# SCH_ONO_R1.net
KiCad netlist of a schematic drawn in EasyEDA
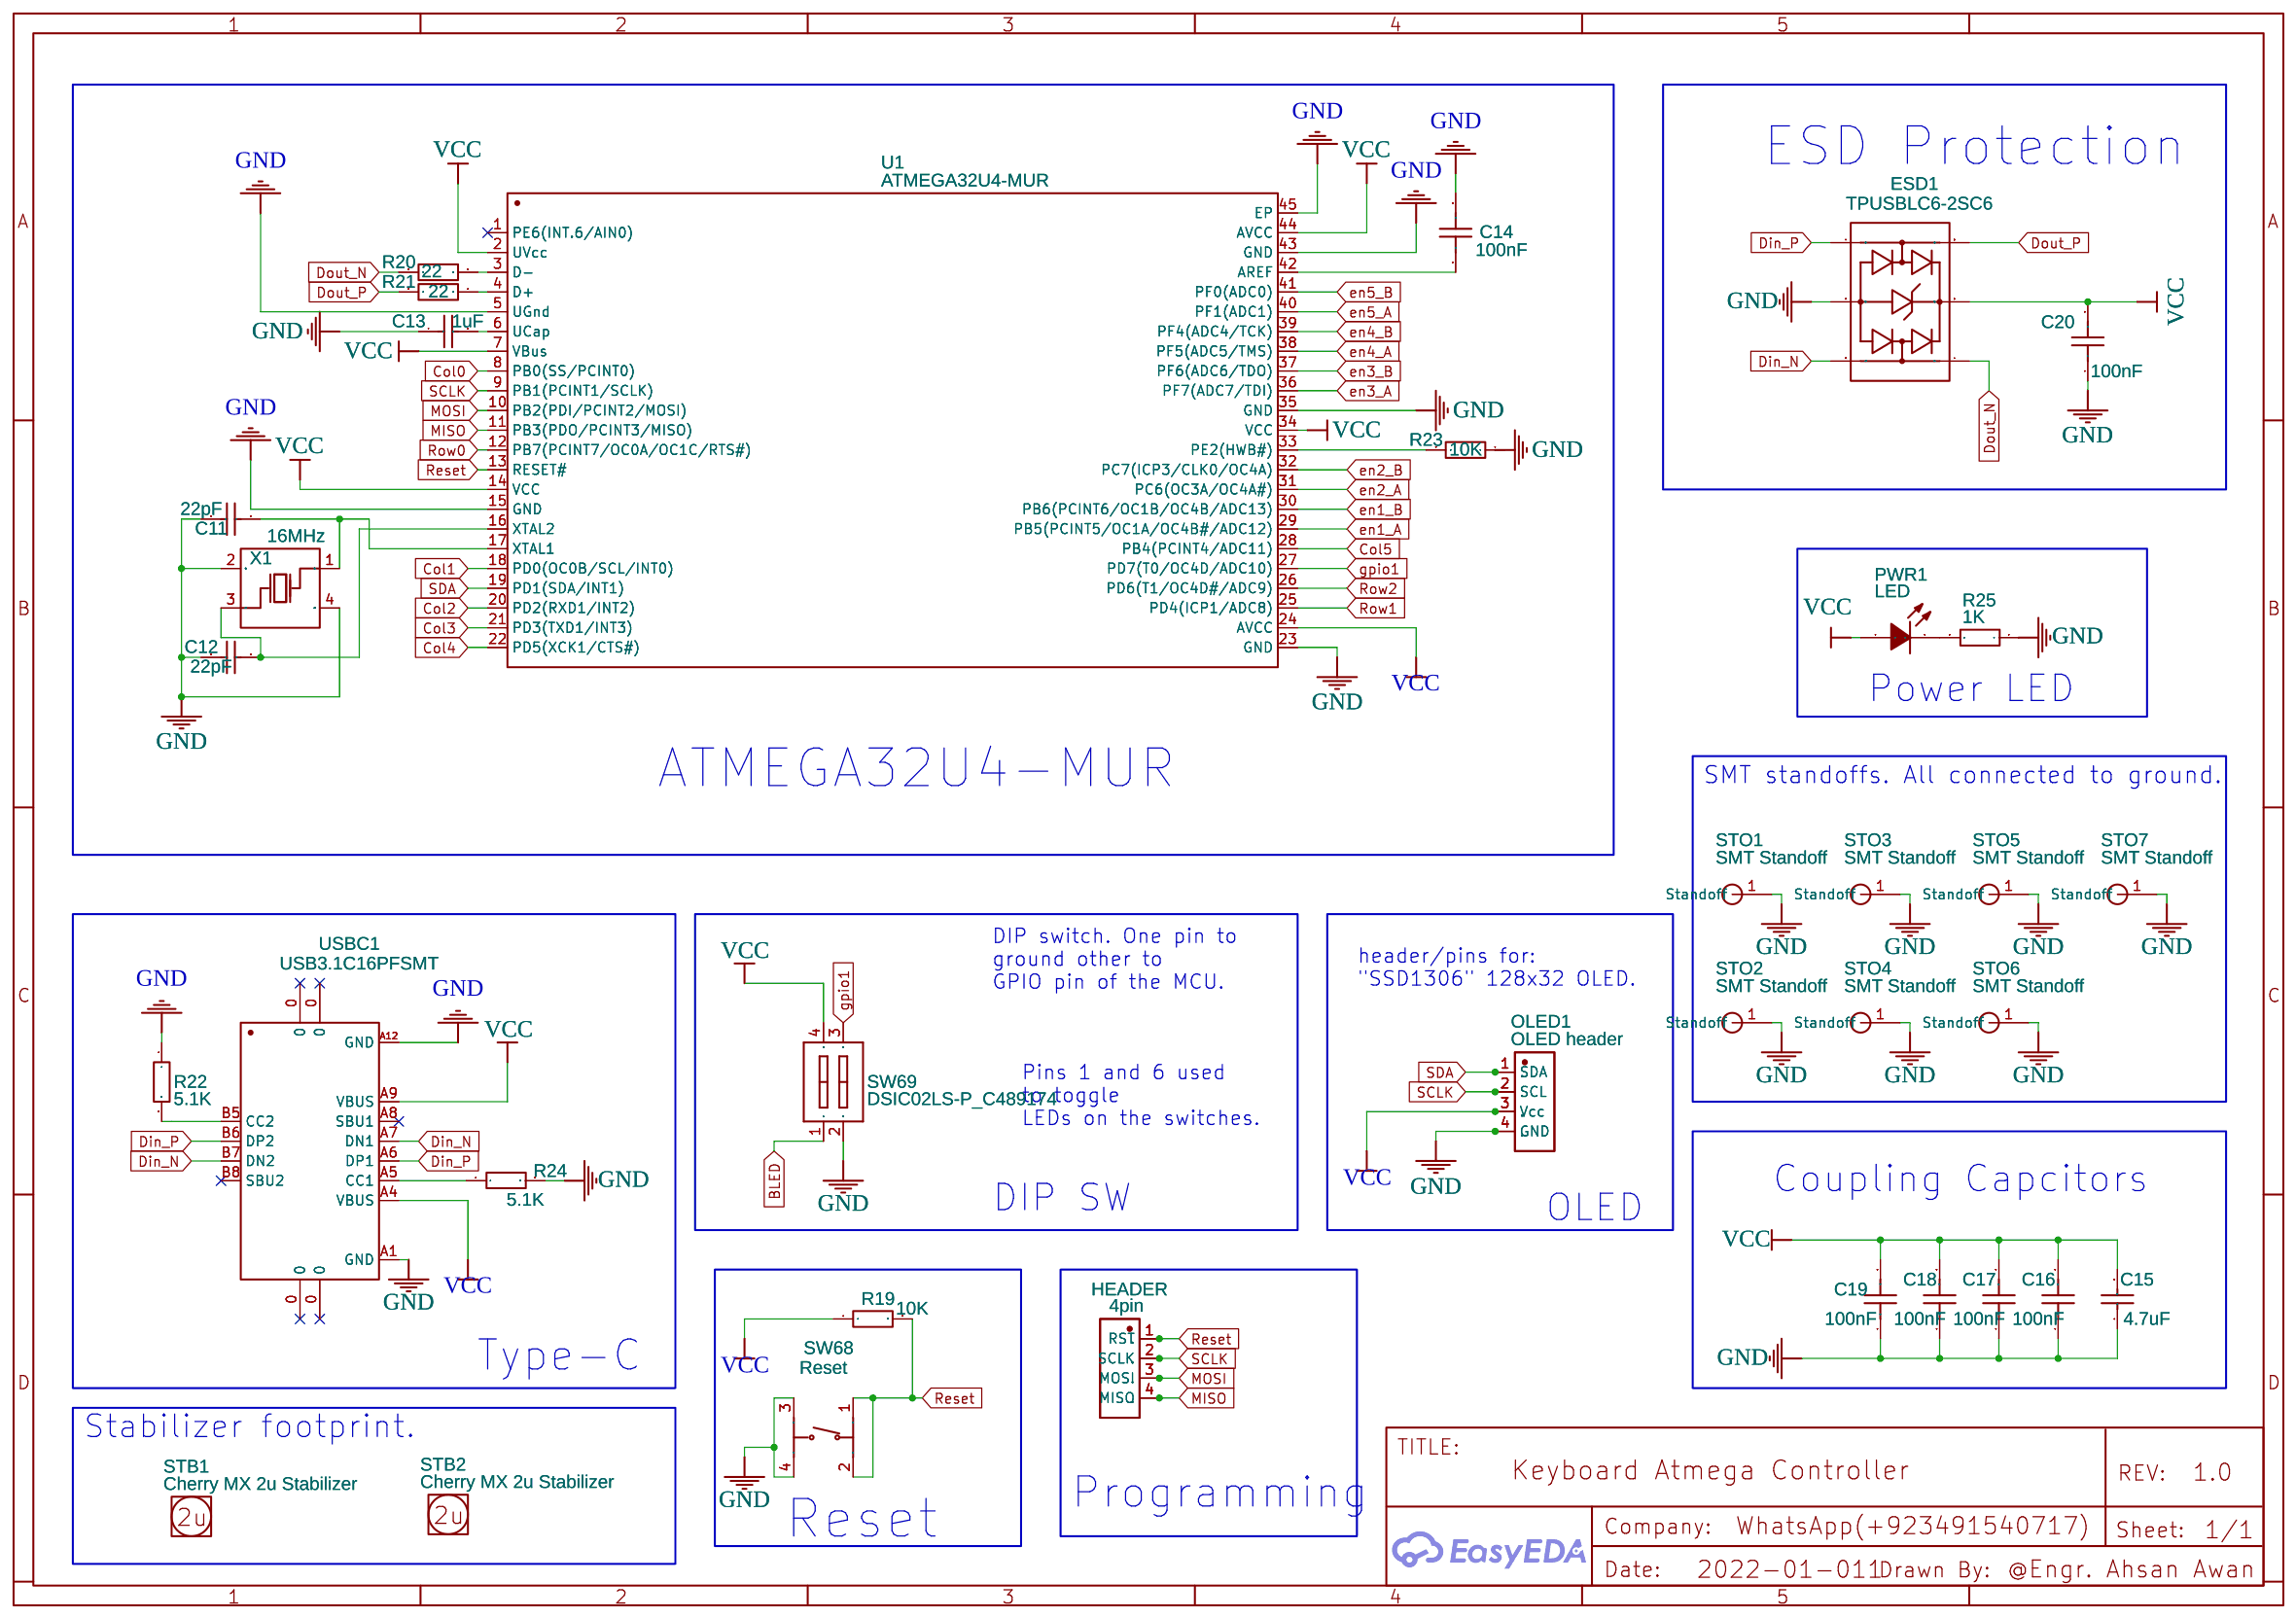
[diagram p0: Atmega MCU]
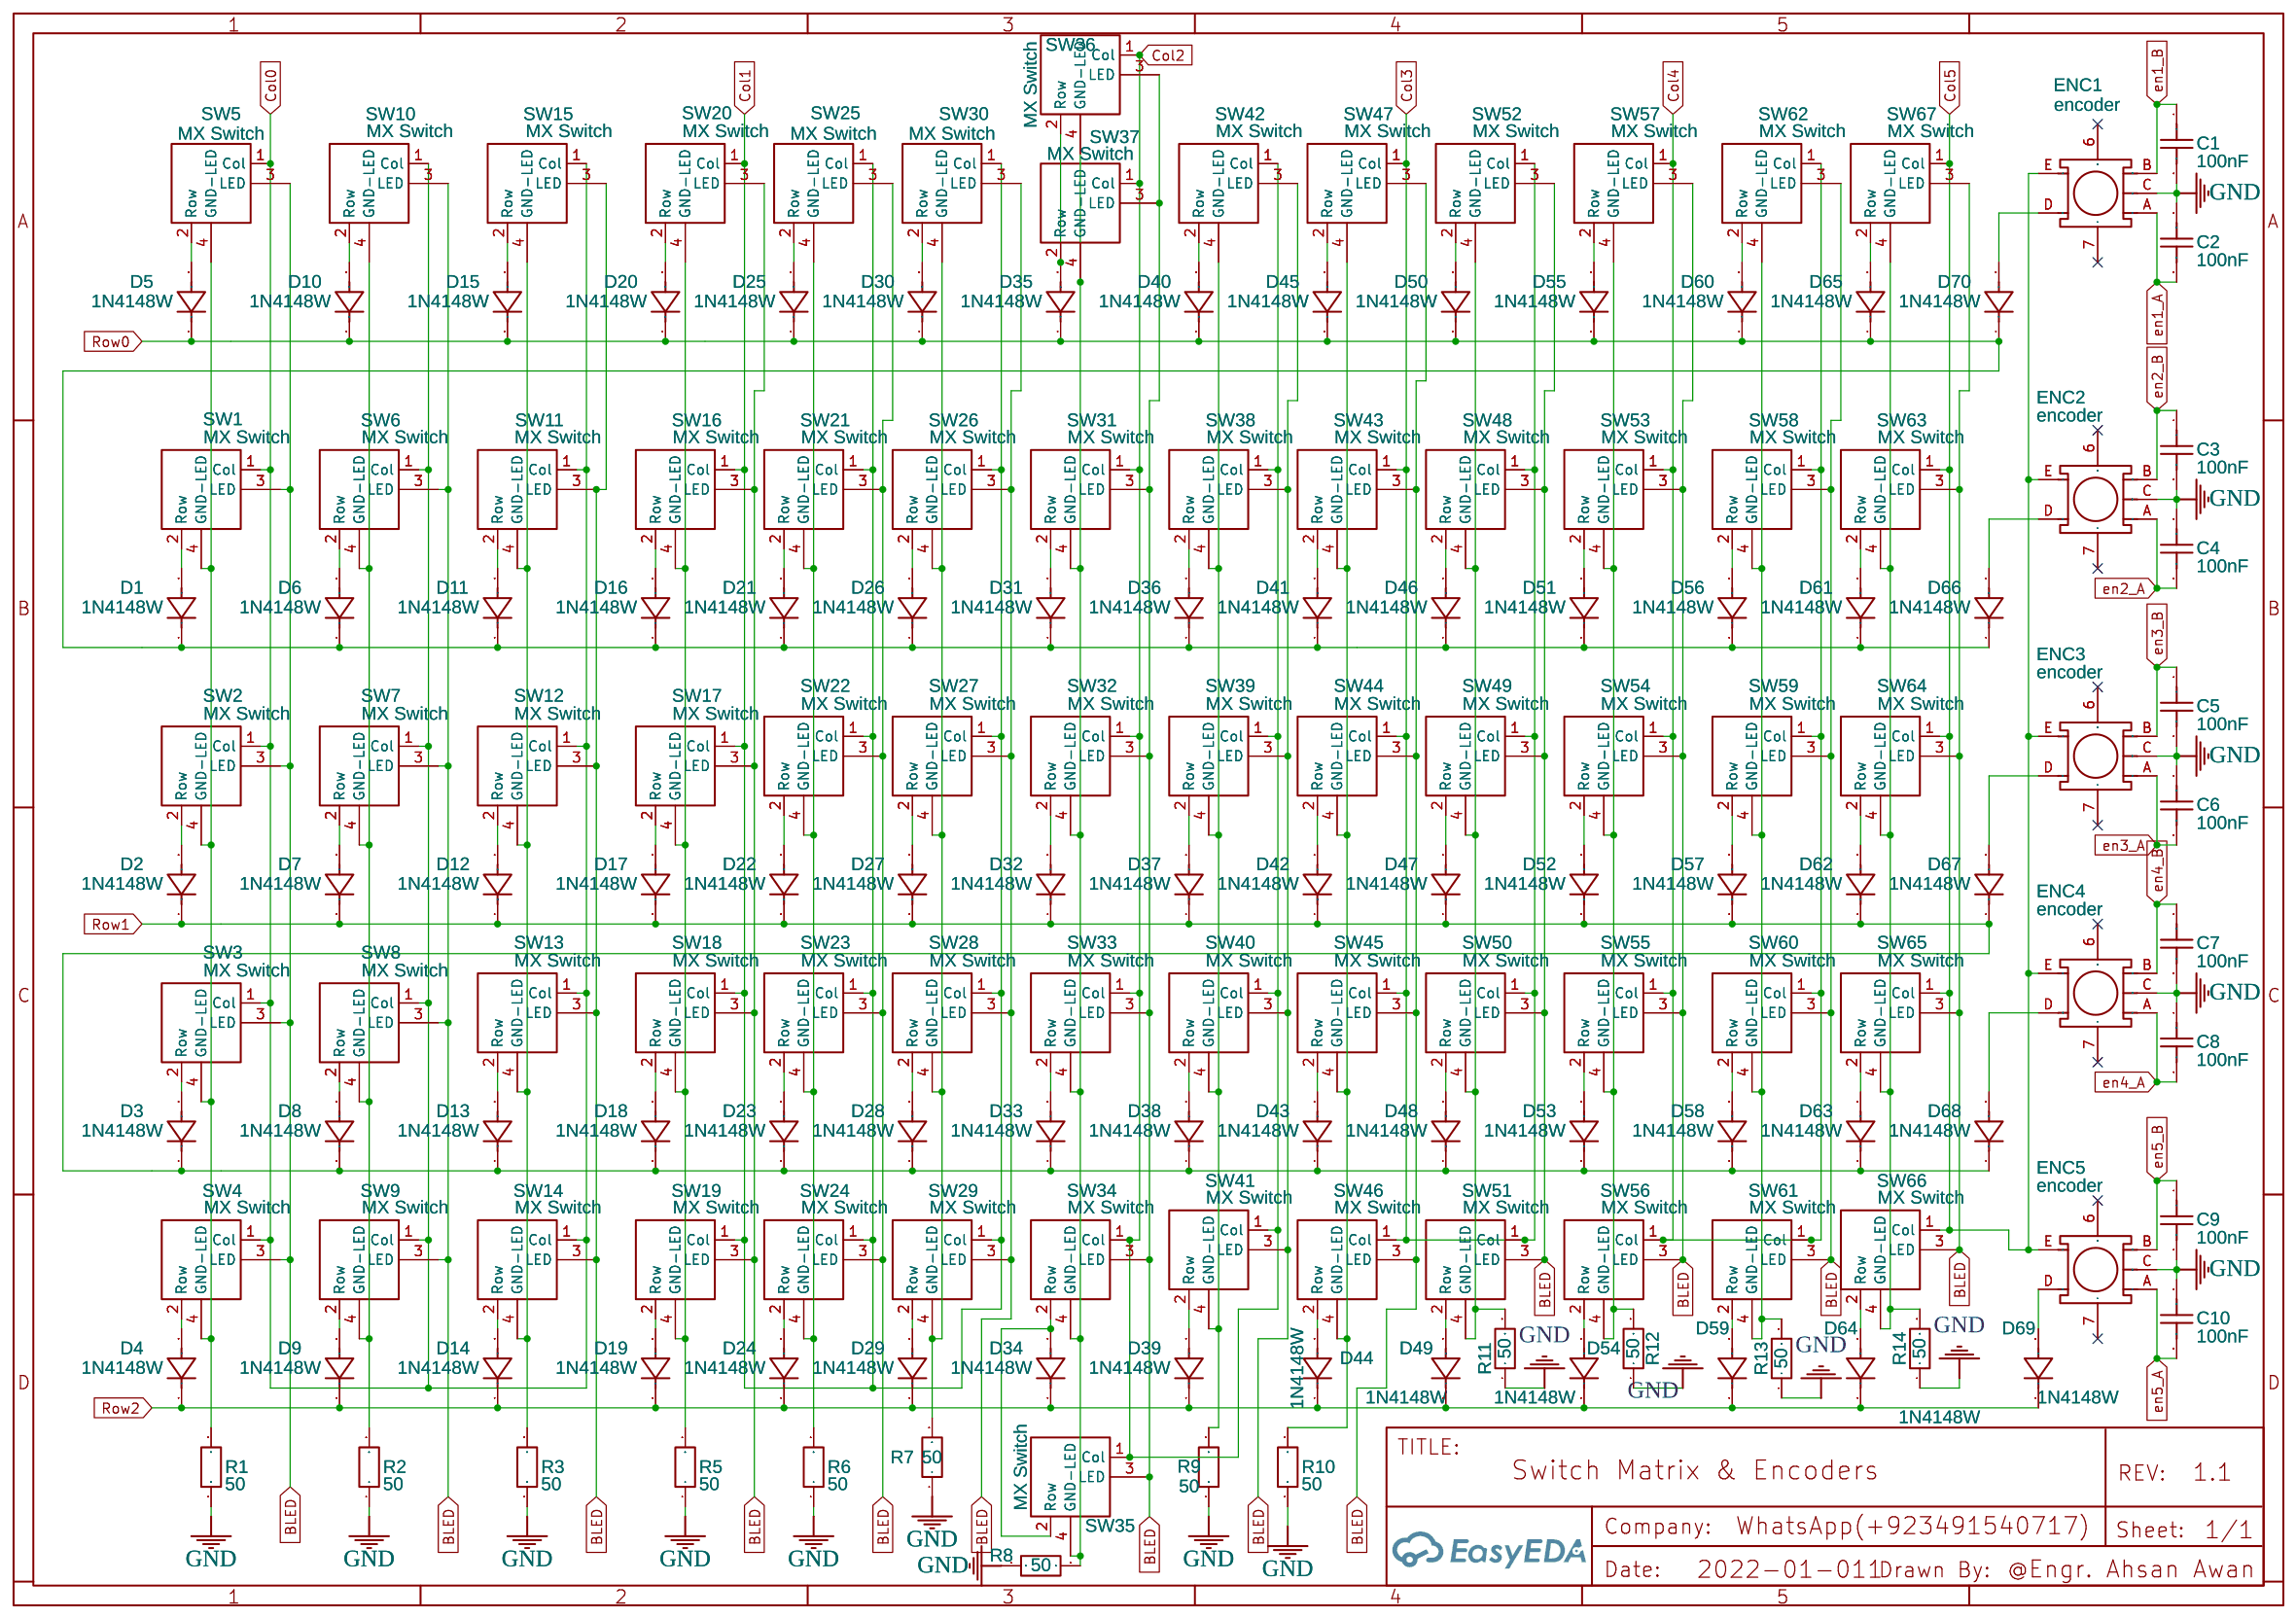
[diagram p1: Switch Matrix]

(export (version "E")
  (design (tool "Eeschema 10.0.6"))
  (components
    (comp (ref "C11")
      (value "22pF")
      (fields
        (field (name "BOM_Manufacturer Part") "CL10C220JB8NNNC")
        (field (name "BOM_Supplier Part") "C1653")
      )
      (libsource (lib "") (part "CL10C220JB8NNNC"))
    )
    (comp (ref "C12")
      (value "22pF")
      (fields
        (field (name "BOM_Manufacturer Part") "CL10C220JB8NNNC")
        (field (name "BOM_Supplier Part") "C1653")
      )
      (libsource (lib "") (part "CL10C220JB8NNNC"))
    )
    (comp (ref "C13")
      (value "1uF")
      (fields
        (field (name "BOM_Manufacturer Part") "CL10A105KB8NNNC")
        (field (name "BOM_Supplier Part") "C15849")
      )
      (libsource (lib "") (part "CL10A105KB8NNNC"))
    )
    (comp (ref "C14")
      (value "100nF")
      (fields
        (field (name "BOM_Manufacturer Part") "CC0603KRX7R9BB104")
        (field (name "BOM_Supplier Part") "C14663")
      )
      (libsource (lib "") (part "CC0603KRX7R9BB104"))
    )
    (comp (ref "C15")
      (value "4.7uF")
      (fields
        (field (name "BOM_Manufacturer Part") "CL10A475KO8NNNC")
        (field (name "BOM_Supplier Part") "C19666")
      )
      (libsource (lib "") (part "CL10A475KO8NNNC"))
    )
    (comp (ref "C16")
      (value "100nF")
      (fields
        (field (name "BOM_Manufacturer Part") "CC0603KRX7R9BB104")
        (field (name "BOM_Supplier Part") "C14663")
      )
      (libsource (lib "") (part "CC0603KRX7R9BB104"))
    )
    (comp (ref "C17")
      (value "100nF")
      (fields
        (field (name "BOM_Manufacturer Part") "CC0603KRX7R9BB104")
        (field (name "BOM_Supplier Part") "C14663")
      )
      (libsource (lib "") (part "CC0603KRX7R9BB104"))
    )
    (comp (ref "C18")
      (value "100nF")
      (fields
        (field (name "BOM_Manufacturer Part") "CC0603KRX7R9BB104")
        (field (name "BOM_Supplier Part") "C14663")
      )
      (libsource (lib "") (part "CC0603KRX7R9BB104"))
    )
    (comp (ref "C19")
      (value "100nF")
      (fields
        (field (name "BOM_Manufacturer Part") "CC0603KRX7R9BB104")
        (field (name "BOM_Supplier Part") "C14663")
      )
      (libsource (lib "") (part "CC0603KRX7R9BB104"))
    )
    (comp (ref "C20")
      (value "100nF")
      (fields
        (field (name "BOM_Manufacturer Part") "CC0603KRX7R9BB104")
        (field (name "BOM_Supplier Part") "C14663")
      )
      (libsource (lib "") (part "CC0603KRX7R9BB104"))
    )
    (comp (ref "ESD1")
      (value "TPUSBLC6-2SC6")
      (fields (field (name "BOM_Supplier Part") "C558442"))
      (libsource (lib "") (part "TPUSBLC6-2SC6"))
    )
    (comp (ref "HEADER")
      (value "4pin")
      (fields
        (field (name "BOM_Manufacturer Part") "X4611WRS-04I-C40D28")
        (field (name "BOM_Supplier Part") "C917591")
      )
      (libsource (lib "") (part "X4611WRS-04I-C40D28_1"))
    )
    (comp (ref "OLED1")
      (value "OLED header")
      (fields
        (field (name "BOM_Manufacturer Part") "X4611WRS-04I-C40D28")
        (field (name "BOM_Supplier Part") "C917591")
      )
      (libsource (lib "") (part "X4611WRS-04I-C40D28"))
    )
    (comp (ref "PWR1")
      (value "LED")
      (fields
        (field (name "BOM_Manufacturer Part") "TJ-S2012SW8TGLC6B-A5")
        (field (name "BOM_Supplier Part") "C192320")
      )
      (libsource (lib "") (part "TJ-S2012SW8TGLC6B-A5"))
    )
    (comp (ref "R19")
      (value "10K")
      (fields
        (field (name "BOM_Manufacturer Part") "0603WAF1002T5E")
        (field (name "BOM_Supplier Part") "C25804")
      )
      (libsource (lib "") (part "0603WAF1002T5E_1"))
    )
    (comp (ref "R20")
      (value "22")
      (fields
        (field (name "BOM_Manufacturer Part") "0603WAF220JT5E")
        (field (name "BOM_Supplier Part") "C23345")
      )
      (libsource (lib "") (part "0603WAF220JT5E"))
    )
    (comp (ref "R21")
      (value "22")
      (fields
        (field (name "BOM_Manufacturer Part") "0603WAF220JT5E")
        (field (name "BOM_Supplier Part") "C23345")
      )
      (libsource (lib "") (part "0603WAF220JT5E"))
    )
    (comp (ref "R22")
      (value "5.1K")
      (fields
        (field (name "BOM_Manufacturer Part") "RMC06035.1K1%N")
        (field (name "BOM_Supplier Part") "C269716")
      )
      (libsource (lib "") (part "RMC06035.1K1%N_1"))
    )
    (comp (ref "R23")
      (value "10K")
      (fields
        (field (name "BOM_Manufacturer Part") "0603WAF1002T5E")
        (field (name "BOM_Supplier Part") "C25804")
      )
      (libsource (lib "") (part "0603WAF1002T5E"))
    )
    (comp (ref "R24")
      (value "5.1K")
      (fields
        (field (name "BOM_Manufacturer Part") "RMC06035.1K1%N")
        (field (name "BOM_Supplier Part") "C269716")
      )
      (libsource (lib "") (part "RMC06035.1K1%N"))
    )
    (comp (ref "R25")
      (value "1K")
      (fields
        (field (name "BOM_Manufacturer Part") "TR0603B1KP0525")
        (field (name "BOM_Supplier Part") "C188364")
      )
      (libsource (lib "") (part "TR0603B1KP0525"))
    )
    (comp (ref "STB1")
      (value "Cherry MX 2u Stabilizer")
      (fields
        (field (name "BOM_Manufacturer Part") "G99-0742")
        (field (name "BOM_Supplier Part") "540-G99-0742")
      )
      (libsource (lib "") (part "Cherry MX 2u Stabilizer"))
    )
    (comp (ref "STB2")
      (value "Cherry MX 2u Stabilizer")
      (fields
        (field (name "BOM_Manufacturer Part") "G99-0742")
        (field (name "BOM_Supplier Part") "540-G99-0742")
      )
      (libsource (lib "") (part "Cherry MX 2u Stabilizer"))
    )
    (comp (ref "STO1")
      (value "SMT Standoff")
      (fields (field (name "BOM_Manufacturer Part") "9774040151R"))
      (libsource (lib "") (part "SMT Standoff"))
    )
    (comp (ref "STO2")
      (value "SMT Standoff")
      (fields (field (name "BOM_Manufacturer Part") "9774040151R"))
      (libsource (lib "") (part "SMT Standoff"))
    )
    (comp (ref "STO3")
      (value "SMT Standoff")
      (fields (field (name "BOM_Manufacturer Part") "9774040151R"))
      (libsource (lib "") (part "SMT Standoff"))
    )
    (comp (ref "STO4")
      (value "SMT Standoff")
      (fields (field (name "BOM_Manufacturer Part") "9774040151R"))
      (libsource (lib "") (part "SMT Standoff"))
    )
    (comp (ref "STO5")
      (value "SMT Standoff")
      (fields (field (name "BOM_Manufacturer Part") "9774040151R"))
      (libsource (lib "") (part "SMT Standoff"))
    )
    (comp (ref "STO6")
      (value "SMT Standoff")
      (fields (field (name "BOM_Manufacturer Part") "9774040151R"))
      (libsource (lib "") (part "SMT Standoff"))
    )
    (comp (ref "STO7")
      (value "SMT Standoff")
      (fields (field (name "BOM_Manufacturer Part") "9774040151R"))
      (libsource (lib "") (part "SMT Standoff"))
    )
    (comp (ref "SW68")
      (value "Reset")
      (fields
        (field (name "BOM_Manufacturer Part") "TS-1187A-B-A-B")
        (field (name "BOM_Supplier Part") "C318884")
      )
      (libsource (lib "") (part "TS-1187A-B-A-B"))
    )
    (comp (ref "SW69")
      (value "DSIC02LS-P_C489174")
      (fields
        (field (name "BOM_Manufacturer Part") "DSIC02LS-P")
        (field (name "BOM_Supplier Part") "C489174")
      )
      (libsource (lib "") (part "DSIC02LS-P_C489174"))
    )
    (comp (ref "U1")
      (value "ATMEGA32U4-MUR")
      (fields (field (name "BOM_Supplier Part") "C45874"))
      (libsource (lib "") (part "ATMEGA32U4-MUR"))
    )
    (comp (ref "U2")
      (value "x")
      (fields
        (field (name "BOM_Manufacturer Part") "PZ2.54-1X4P-ZW")
        (field (name "BOM_Supplier Part") "C2837836")
      )
      (libsource (lib "") (part "PZ2.54-1X4P-ZW"))
    )
    (comp (ref "U3")
      (value "x")
      (fields
        (field (name "BOM_Manufacturer Part") "PZ2.54-1X4P-ZW")
        (field (name "BOM_Supplier Part") "C2837836")
      )
      (libsource (lib "") (part "PZ2.54-1X4P-ZW_1"))
    )
    (comp (ref "USBC1")
      (value "USB3.1C16PFSMT")
      (fields (field (name "BOM_Supplier Part") "C167321"))
      (libsource (lib "") (part "USB3.1C16PFSMT"))
    )
    (comp (ref "X1")
      (value "16MHz")
      (fields
        (field (name "BOM_Manufacturer Part") "X322516MLB4SI")
        (field (name "BOM_Supplier Part") "C13738")
      )
      (libsource (lib "") (part "X322516MLB4SI"))
    )
    (comp (ref "C1")
      (value "100nF")
      (fields
        (field (name "BOM_Manufacturer Part") "CC0603KRX7R9BB104")
        (field (name "BOM_Supplier Part") "C14663")
      )
      (libsource (lib "") (part "CC0603KRX7R9BB104"))
    )
    (comp (ref "C2")
      (value "100nF")
      (fields
        (field (name "BOM_Manufacturer Part") "CC0603KRX7R9BB104")
        (field (name "BOM_Supplier Part") "C14663")
      )
      (libsource (lib "") (part "CC0603KRX7R9BB104"))
    )
    (comp (ref "C3")
      (value "100nF")
      (fields
        (field (name "BOM_Manufacturer Part") "CC0603KRX7R9BB104")
        (field (name "BOM_Supplier Part") "C14663")
      )
      (libsource (lib "") (part "CC0603KRX7R9BB104"))
    )
    (comp (ref "C4")
      (value "100nF")
      (fields
        (field (name "BOM_Manufacturer Part") "CC0603KRX7R9BB104")
        (field (name "BOM_Supplier Part") "C14663")
      )
      (libsource (lib "") (part "CC0603KRX7R9BB104"))
    )
    (comp (ref "C5")
      (value "100nF")
      (fields
        (field (name "BOM_Manufacturer Part") "CC0603KRX7R9BB104")
        (field (name "BOM_Supplier Part") "C14663")
      )
      (libsource (lib "") (part "CC0603KRX7R9BB104"))
    )
    (comp (ref "C6")
      (value "100nF")
      (fields
        (field (name "BOM_Manufacturer Part") "CC0603KRX7R9BB104")
        (field (name "BOM_Supplier Part") "C14663")
      )
      (libsource (lib "") (part "CC0603KRX7R9BB104"))
    )
    (comp (ref "C7")
      (value "100nF")
      (fields
        (field (name "BOM_Manufacturer Part") "CC0603KRX7R9BB104")
        (field (name "BOM_Supplier Part") "C14663")
      )
      (libsource (lib "") (part "CC0603KRX7R9BB104"))
    )
    (comp (ref "C8")
      (value "100nF")
      (fields
        (field (name "BOM_Manufacturer Part") "CC0603KRX7R9BB104")
        (field (name "BOM_Supplier Part") "C14663")
      )
      (libsource (lib "") (part "CC0603KRX7R9BB104"))
    )
    (comp (ref "C9")
      (value "100nF")
      (fields
        (field (name "BOM_Manufacturer Part") "CC0603KRX7R9BB104")
        (field (name "BOM_Supplier Part") "C14663")
      )
      (libsource (lib "") (part "CC0603KRX7R9BB104"))
    )
    (comp (ref "C10")
      (value "100nF")
      (fields
        (field (name "BOM_Manufacturer Part") "CC0603KRX7R9BB104")
        (field (name "BOM_Supplier Part") "C14663")
      )
      (libsource (lib "") (part "CC0603KRX7R9BB104"))
    )
    (comp (ref "D1")
      (value "1N4148W")
      (fields (field (name "BOM_Supplier Part") "C2828417"))
      (libsource (lib "") (part "1N4148W_C2828417"))
    )
    (comp (ref "D2")
      (value "1N4148W")
      (fields (field (name "BOM_Supplier Part") "C2828417"))
      (libsource (lib "") (part "1N4148W_C2828417"))
    )
    (comp (ref "D3")
      (value "1N4148W")
      (fields (field (name "BOM_Supplier Part") "C2828417"))
      (libsource (lib "") (part "1N4148W_C2828417"))
    )
    (comp (ref "D4")
      (value "1N4148W")
      (fields (field (name "BOM_Supplier Part") "C2828417"))
      (libsource (lib "") (part "1N4148W_C2828417"))
    )
    (comp (ref "D5")
      (value "1N4148W")
      (fields (field (name "BOM_Supplier Part") "C2828417"))
      (libsource (lib "") (part "1N4148W_C2828417"))
    )
    (comp (ref "D6")
      (value "1N4148W")
      (fields (field (name "BOM_Supplier Part") "C2828417"))
      (libsource (lib "") (part "1N4148W_C2828417"))
    )
    (comp (ref "D7")
      (value "1N4148W")
      (fields (field (name "BOM_Supplier Part") "C2828417"))
      (libsource (lib "") (part "1N4148W_C2828417"))
    )
    (comp (ref "D8")
      (value "1N4148W")
      (fields (field (name "BOM_Supplier Part") "C2828417"))
      (libsource (lib "") (part "1N4148W_C2828417"))
    )
    (comp (ref "D9")
      (value "1N4148W")
      (fields (field (name "BOM_Supplier Part") "C2828417"))
      (libsource (lib "") (part "1N4148W_C2828417"))
    )
    (comp (ref "D10")
      (value "1N4148W")
      (fields (field (name "BOM_Supplier Part") "C2828417"))
      (libsource (lib "") (part "1N4148W_C2828417"))
    )
    (comp (ref "D11")
      (value "1N4148W")
      (fields (field (name "BOM_Supplier Part") "C2828417"))
      (libsource (lib "") (part "1N4148W_C2828417"))
    )
    (comp (ref "D12")
      (value "1N4148W")
      (fields (field (name "BOM_Supplier Part") "C2828417"))
      (libsource (lib "") (part "1N4148W_C2828417"))
    )
    (comp (ref "D13")
      (value "1N4148W")
      (fields (field (name "BOM_Supplier Part") "C2828417"))
      (libsource (lib "") (part "1N4148W_C2828417"))
    )
    (comp (ref "D14")
      (value "1N4148W")
      (fields (field (name "BOM_Supplier Part") "C2828417"))
      (libsource (lib "") (part "1N4148W_C2828417"))
    )
    (comp (ref "D15")
      (value "1N4148W")
      (fields (field (name "BOM_Supplier Part") "C2828417"))
      (libsource (lib "") (part "1N4148W_C2828417"))
    )
    (comp (ref "D16")
      (value "1N4148W")
      (fields (field (name "BOM_Supplier Part") "C2828417"))
      (libsource (lib "") (part "1N4148W_C2828417"))
    )
    (comp (ref "D17")
      (value "1N4148W")
      (fields (field (name "BOM_Supplier Part") "C2828417"))
      (libsource (lib "") (part "1N4148W_C2828417"))
    )
    (comp (ref "D18")
      (value "1N4148W")
      (fields (field (name "BOM_Supplier Part") "C2828417"))
      (libsource (lib "") (part "1N4148W_C2828417"))
    )
    (comp (ref "D19")
      (value "1N4148W")
      (fields (field (name "BOM_Supplier Part") "C2828417"))
      (libsource (lib "") (part "1N4148W_C2828417"))
    )
    (comp (ref "D20")
      (value "1N4148W")
      (fields (field (name "BOM_Supplier Part") "C2828417"))
      (libsource (lib "") (part "1N4148W_C2828417"))
    )
    (comp (ref "D21")
      (value "1N4148W")
      (fields (field (name "BOM_Supplier Part") "C2828417"))
      (libsource (lib "") (part "1N4148W_C2828417"))
    )
    (comp (ref "D22")
      (value "1N4148W")
      (fields (field (name "BOM_Supplier Part") "C2828417"))
      (libsource (lib "") (part "1N4148W_C2828417"))
    )
    (comp (ref "D23")
      (value "1N4148W")
      (fields (field (name "BOM_Supplier Part") "C2828417"))
      (libsource (lib "") (part "1N4148W_C2828417"))
    )
    (comp (ref "D24")
      (value "1N4148W")
      (fields (field (name "BOM_Supplier Part") "C2828417"))
      (libsource (lib "") (part "1N4148W_C2828417"))
    )
    (comp (ref "D25")
      (value "1N4148W")
      (fields (field (name "BOM_Supplier Part") "C2828417"))
      (libsource (lib "") (part "1N4148W_C2828417"))
    )
    (comp (ref "D26")
      (value "1N4148W")
      (fields (field (name "BOM_Supplier Part") "C2828417"))
      (libsource (lib "") (part "1N4148W_C2828417"))
    )
    (comp (ref "D27")
      (value "1N4148W")
      (fields (field (name "BOM_Supplier Part") "C2828417"))
      (libsource (lib "") (part "1N4148W_C2828417"))
    )
    (comp (ref "D28")
      (value "1N4148W")
      (fields (field (name "BOM_Supplier Part") "C2828417"))
      (libsource (lib "") (part "1N4148W_C2828417"))
    )
    (comp (ref "D29")
      (value "1N4148W")
      (fields (field (name "BOM_Supplier Part") "C2828417"))
      (libsource (lib "") (part "1N4148W_C2828417"))
    )
    (comp (ref "D30")
      (value "1N4148W")
      (fields (field (name "BOM_Supplier Part") "C2828417"))
      (libsource (lib "") (part "1N4148W_C2828417"))
    )
    (comp (ref "D31")
      (value "1N4148W")
      (fields (field (name "BOM_Supplier Part") "C2828417"))
      (libsource (lib "") (part "1N4148W_C2828417"))
    )
    (comp (ref "D32")
      (value "1N4148W")
      (fields (field (name "BOM_Supplier Part") "C2828417"))
      (libsource (lib "") (part "1N4148W_C2828417"))
    )
    (comp (ref "D33")
      (value "1N4148W")
      (fields (field (name "BOM_Supplier Part") "C2828417"))
      (libsource (lib "") (part "1N4148W_C2828417"))
    )
    (comp (ref "D34")
      (value "1N4148W")
      (fields (field (name "BOM_Supplier Part") "C2828417"))
      (libsource (lib "") (part "1N4148W_C2828417"))
    )
    (comp (ref "D35")
      (value "1N4148W")
      (fields (field (name "BOM_Supplier Part") "C2828417"))
      (libsource (lib "") (part "1N4148W_C2828417"))
    )
    (comp (ref "D36")
      (value "1N4148W")
      (fields (field (name "BOM_Supplier Part") "C2828417"))
      (libsource (lib "") (part "1N4148W_C2828417"))
    )
    (comp (ref "D37")
      (value "1N4148W")
      (fields (field (name "BOM_Supplier Part") "C2828417"))
      (libsource (lib "") (part "1N4148W_C2828417"))
    )
    (comp (ref "D38")
      (value "1N4148W")
      (fields (field (name "BOM_Supplier Part") "C2828417"))
      (libsource (lib "") (part "1N4148W_C2828417"))
    )
    (comp (ref "D39")
      (value "1N4148W")
      (fields (field (name "BOM_Supplier Part") "C2828417"))
      (libsource (lib "") (part "1N4148W_C2828417"))
    )
    (comp (ref "D40")
      (value "1N4148W")
      (fields (field (name "BOM_Supplier Part") "C2828417"))
      (libsource (lib "") (part "1N4148W_C2828417"))
    )
    (comp (ref "D41")
      (value "1N4148W")
      (fields (field (name "BOM_Supplier Part") "C2828417"))
      (libsource (lib "") (part "1N4148W_C2828417"))
    )
    (comp (ref "D42")
      (value "1N4148W")
      (fields (field (name "BOM_Supplier Part") "C2828417"))
      (libsource (lib "") (part "1N4148W_C2828417"))
    )
    (comp (ref "D43")
      (value "1N4148W")
      (fields (field (name "BOM_Supplier Part") "C2828417"))
      (libsource (lib "") (part "1N4148W_C2828417"))
    )
    (comp (ref "D44")
      (value "1N4148W")
      (fields (field (name "BOM_Supplier Part") "C2828417"))
      (libsource (lib "") (part "1N4148W_C2828417"))
    )
    (comp (ref "D45")
      (value "1N4148W")
      (fields (field (name "BOM_Supplier Part") "C2828417"))
      (libsource (lib "") (part "1N4148W_C2828417"))
    )
    (comp (ref "D46")
      (value "1N4148W")
      (fields (field (name "BOM_Supplier Part") "C2828417"))
      (libsource (lib "") (part "1N4148W_C2828417"))
    )
    (comp (ref "D47")
      (value "1N4148W")
      (fields (field (name "BOM_Supplier Part") "C2828417"))
      (libsource (lib "") (part "1N4148W_C2828417"))
    )
    (comp (ref "D48")
      (value "1N4148W")
      (fields (field (name "BOM_Supplier Part") "C2828417"))
      (libsource (lib "") (part "1N4148W_C2828417"))
    )
    (comp (ref "D49")
      (value "1N4148W")
      (fields (field (name "BOM_Supplier Part") "C2828417"))
      (libsource (lib "") (part "1N4148W_C2828417"))
    )
    (comp (ref "D50")
      (value "1N4148W")
      (fields (field (name "BOM_Supplier Part") "C2828417"))
      (libsource (lib "") (part "1N4148W_C2828417"))
    )
    (comp (ref "D51")
      (value "1N4148W")
      (fields (field (name "BOM_Supplier Part") "C2828417"))
      (libsource (lib "") (part "1N4148W_C2828417"))
    )
    (comp (ref "D52")
      (value "1N4148W")
      (fields (field (name "BOM_Supplier Part") "C2828417"))
      (libsource (lib "") (part "1N4148W_C2828417"))
    )
    (comp (ref "D53")
      (value "1N4148W")
      (fields (field (name "BOM_Supplier Part") "C2828417"))
      (libsource (lib "") (part "1N4148W_C2828417"))
    )
    (comp (ref "D54")
      (value "1N4148W")
      (fields (field (name "BOM_Supplier Part") "C2828417"))
      (libsource (lib "") (part "1N4148W_C2828417"))
    )
    (comp (ref "D55")
      (value "1N4148W")
      (fields (field (name "BOM_Supplier Part") "C2828417"))
      (libsource (lib "") (part "1N4148W_C2828417"))
    )
    (comp (ref "D56")
      (value "1N4148W")
      (fields (field (name "BOM_Supplier Part") "C2828417"))
      (libsource (lib "") (part "1N4148W_C2828417"))
    )
    (comp (ref "D57")
      (value "1N4148W")
      (fields (field (name "BOM_Supplier Part") "C2828417"))
      (libsource (lib "") (part "1N4148W_C2828417"))
    )
    (comp (ref "D58")
      (value "1N4148W")
      (fields (field (name "BOM_Supplier Part") "C2828417"))
      (libsource (lib "") (part "1N4148W_C2828417"))
    )
    (comp (ref "D59")
      (value "1N4148W")
      (fields (field (name "BOM_Supplier Part") "C2828417"))
      (libsource (lib "") (part "1N4148W_C2828417"))
    )
    (comp (ref "D60")
      (value "1N4148W")
      (fields (field (name "BOM_Supplier Part") "C2828417"))
      (libsource (lib "") (part "1N4148W_C2828417"))
    )
    (comp (ref "D61")
      (value "1N4148W")
      (fields (field (name "BOM_Supplier Part") "C2828417"))
      (libsource (lib "") (part "1N4148W_C2828417"))
    )
    (comp (ref "D62")
      (value "1N4148W")
      (fields (field (name "BOM_Supplier Part") "C2828417"))
      (libsource (lib "") (part "1N4148W_C2828417"))
    )
    (comp (ref "D63")
      (value "1N4148W")
      (fields (field (name "BOM_Supplier Part") "C2828417"))
      (libsource (lib "") (part "1N4148W_C2828417"))
    )
    (comp (ref "D64")
      (value "1N4148W")
      (fields (field (name "BOM_Supplier Part") "C2828417"))
      (libsource (lib "") (part "1N4148W_C2828417"))
    )
    (comp (ref "D65")
      (value "1N4148W")
      (fields (field (name "BOM_Supplier Part") "C2828417"))
      (libsource (lib "") (part "1N4148W_C2828417"))
    )
    (comp (ref "D66")
      (value "1N4148W")
      (fields (field (name "BOM_Supplier Part") "C2828417"))
      (libsource (lib "") (part "1N4148W_C2828417"))
    )
    (comp (ref "D67")
      (value "1N4148W")
      (fields (field (name "BOM_Supplier Part") "C2828417"))
      (libsource (lib "") (part "1N4148W_C2828417"))
    )
    (comp (ref "D68")
      (value "1N4148W")
      (fields (field (name "BOM_Supplier Part") "C2828417"))
      (libsource (lib "") (part "1N4148W_C2828417"))
    )
    (comp (ref "D69")
      (value "1N4148W")
      (fields (field (name "BOM_Supplier Part") "C2828417"))
      (libsource (lib "") (part "1N4148W_C2828417"))
    )
    (comp (ref "D70")
      (value "1N4148W")
      (fields (field (name "BOM_Supplier Part") "C2828417"))
      (libsource (lib "") (part "1N4148W_C2828417"))
    )
    (comp (ref "ENC1")
      (value "encoder")
      (fields
        (field (name "BOM_Manufacturer Part") "EC11E18244AU")
        (field (name "BOM_Supplier Part") "C202365")
      )
      (libsource (lib "") (part "EC11E18244AU"))
    )
    (comp (ref "ENC2")
      (value "encoder")
      (fields
        (field (name "BOM_Manufacturer Part") "EC11E18244AU")
        (field (name "BOM_Supplier Part") "C202365")
      )
      (libsource (lib "") (part "EC11E18244AU"))
    )
    (comp (ref "ENC3")
      (value "encoder")
      (fields
        (field (name "BOM_Manufacturer Part") "EC11E18244AU")
        (field (name "BOM_Supplier Part") "C202365")
      )
      (libsource (lib "") (part "EC11E18244AU"))
    )
    (comp (ref "ENC4")
      (value "encoder")
      (fields
        (field (name "BOM_Manufacturer Part") "EC11E18244AU")
        (field (name "BOM_Supplier Part") "C202365")
      )
      (libsource (lib "") (part "EC11E18244AU"))
    )
    (comp (ref "ENC5")
      (value "encoder")
      (fields
        (field (name "BOM_Manufacturer Part") "EC11E18244AU")
        (field (name "BOM_Supplier Part") "C202365")
      )
      (libsource (lib "") (part "EC11E18244AU"))
    )
    (comp (ref "R1")
      (value "50")
      (fields
        (field (name "BOM_Manufacturer Part") "HP03W5F500JT5E")
        (field (name "BOM_Supplier Part") "C2759402")
      )
      (libsource (lib "") (part "HP03W5F500JT5E"))
    )
    (comp (ref "R2")
      (value "50")
      (fields
        (field (name "BOM_Manufacturer Part") "HP03W5F500JT5E")
        (field (name "BOM_Supplier Part") "C2759402")
      )
      (libsource (lib "") (part "HP03W5F500JT5E"))
    )
    (comp (ref "R3")
      (value "50")
      (fields
        (field (name "BOM_Manufacturer Part") "HP03W5F500JT5E")
        (field (name "BOM_Supplier Part") "C2759402")
      )
      (libsource (lib "") (part "HP03W5F500JT5E"))
    )
    (comp (ref "R5")
      (value "50")
      (fields
        (field (name "BOM_Manufacturer Part") "HP03W5F500JT5E")
        (field (name "BOM_Supplier Part") "C2759402")
      )
      (libsource (lib "") (part "HP03W5F500JT5E"))
    )
    (comp (ref "R6")
      (value "50")
      (fields
        (field (name "BOM_Manufacturer Part") "HP03W5F500JT5E")
        (field (name "BOM_Supplier Part") "C2759402")
      )
      (libsource (lib "") (part "HP03W5F500JT5E"))
    )
    (comp (ref "R7")
      (value "50")
      (fields
        (field (name "BOM_Manufacturer Part") "HP03W5F500JT5E")
        (field (name "BOM_Supplier Part") "C2759402")
      )
      (libsource (lib "") (part "HP03W5F500JT5E"))
    )
    (comp (ref "R8")
      (value "50")
      (fields
        (field (name "BOM_Manufacturer Part") "HP03W5F500JT5E")
        (field (name "BOM_Supplier Part") "C2759402")
      )
      (libsource (lib "") (part "HP03W5F500JT5E_1"))
    )
    (comp (ref "R9")
      (value "50")
      (fields
        (field (name "BOM_Manufacturer Part") "HP03W5F500JT5E")
        (field (name "BOM_Supplier Part") "C2759402")
      )
      (libsource (lib "") (part "HP03W5F500JT5E"))
    )
    (comp (ref "R10")
      (value "50")
      (fields
        (field (name "BOM_Manufacturer Part") "HP03W5F500JT5E")
        (field (name "BOM_Supplier Part") "C2759402")
      )
      (libsource (lib "") (part "HP03W5F500JT5E"))
    )
    (comp (ref "R11")
      (value "50")
      (fields
        (field (name "BOM_Manufacturer Part") "HP03W5F500JT5E")
        (field (name "BOM_Supplier Part") "C2759402")
      )
      (libsource (lib "") (part "HP03W5F500JT5E"))
    )
    (comp (ref "R12")
      (value "50")
      (fields
        (field (name "BOM_Manufacturer Part") "HP03W5F500JT5E")
        (field (name "BOM_Supplier Part") "C2759402")
      )
      (libsource (lib "") (part "HP03W5F500JT5E"))
    )
    (comp (ref "R13")
      (value "50")
      (fields
        (field (name "BOM_Manufacturer Part") "HP03W5F500JT5E")
        (field (name "BOM_Supplier Part") "C2759402")
      )
      (libsource (lib "") (part "HP03W5F500JT5E"))
    )
    (comp (ref "R14")
      (value "50")
      (fields
        (field (name "BOM_Manufacturer Part") "HP03W5F500JT5E")
        (field (name "BOM_Supplier Part") "C2759402")
      )
      (libsource (lib "") (part "HP03W5F500JT5E"))
    )
    (comp (ref "SW1")
      (value "MX Switch")
      (fields (field (name "BOM_Supplier Part") "Cherry MX or Alps/Matias switch"))
      (libsource (lib "") (part "MX Switch"))
    )
    (comp (ref "SW2")
      (value "MX Switch")
      (fields (field (name "BOM_Supplier Part") "Cherry MX or Alps/Matias switch"))
      (libsource (lib "") (part "MX Switch"))
    )
    (comp (ref "SW3")
      (value "MX Switch")
      (fields (field (name "BOM_Supplier Part") "Cherry MX or Alps/Matias switch"))
      (libsource (lib "") (part "MX Switch"))
    )
    (comp (ref "SW4")
      (value "MX Switch")
      (fields (field (name "BOM_Supplier Part") "Cherry MX or Alps/Matias switch"))
      (libsource (lib "") (part "MX Switch"))
    )
    (comp (ref "SW5")
      (value "MX Switch")
      (fields (field (name "BOM_Supplier Part") "Cherry MX or Alps/Matias switch"))
      (libsource (lib "") (part "MX Switch"))
    )
    (comp (ref "SW6")
      (value "MX Switch")
      (fields (field (name "BOM_Supplier Part") "Cherry MX or Alps/Matias switch"))
      (libsource (lib "") (part "MX Switch"))
    )
    (comp (ref "SW7")
      (value "MX Switch")
      (fields (field (name "BOM_Supplier Part") "Cherry MX or Alps/Matias switch"))
      (libsource (lib "") (part "MX Switch"))
    )
    (comp (ref "SW8")
      (value "MX Switch")
      (fields (field (name "BOM_Supplier Part") "Cherry MX or Alps/Matias switch"))
      (libsource (lib "") (part "MX Switch"))
    )
    (comp (ref "SW9")
      (value "MX Switch")
      (fields (field (name "BOM_Supplier Part") "Cherry MX or Alps/Matias switch"))
      (libsource (lib "") (part "MX Switch"))
    )
    (comp (ref "SW10")
      (value "MX Switch")
      (fields (field (name "BOM_Supplier Part") "Cherry MX or Alps/Matias switch"))
      (libsource (lib "") (part "MX Switch"))
    )
    (comp (ref "SW11")
      (value "MX Switch")
      (fields (field (name "BOM_Supplier Part") "Cherry MX or Alps/Matias switch"))
      (libsource (lib "") (part "MX Switch"))
    )
    (comp (ref "SW12")
      (value "MX Switch")
      (fields (field (name "BOM_Supplier Part") "Cherry MX or Alps/Matias switch"))
      (libsource (lib "") (part "MX Switch"))
    )
    (comp (ref "SW13")
      (value "MX Switch")
      (fields (field (name "BOM_Supplier Part") "Cherry MX or Alps/Matias switch"))
      (libsource (lib "") (part "MX Switch"))
    )
    (comp (ref "SW14")
      (value "MX Switch")
      (fields (field (name "BOM_Supplier Part") "Cherry MX or Alps/Matias switch"))
      (libsource (lib "") (part "MX Switch"))
    )
    (comp (ref "SW15")
      (value "MX Switch")
      (fields (field (name "BOM_Supplier Part") "Cherry MX or Alps/Matias switch"))
      (libsource (lib "") (part "MX Switch"))
    )
    (comp (ref "SW16")
      (value "MX Switch")
      (fields (field (name "BOM_Supplier Part") "Cherry MX or Alps/Matias switch"))
      (libsource (lib "") (part "MX Switch"))
    )
    (comp (ref "SW17")
      (value "MX Switch")
      (fields (field (name "BOM_Supplier Part") "Cherry MX or Alps/Matias switch"))
      (libsource (lib "") (part "MX Switch"))
    )
    (comp (ref "SW18")
      (value "MX Switch")
      (fields (field (name "BOM_Supplier Part") "Cherry MX or Alps/Matias switch"))
      (libsource (lib "") (part "MX Switch"))
    )
    (comp (ref "SW19")
      (value "MX Switch")
      (fields (field (name "BOM_Supplier Part") "Cherry MX or Alps/Matias switch"))
      (libsource (lib "") (part "MX Switch"))
    )
    (comp (ref "SW20")
      (value "MX Switch")
      (fields (field (name "BOM_Supplier Part") "Cherry MX or Alps/Matias switch"))
      (libsource (lib "") (part "MX Switch"))
    )
    (comp (ref "SW21")
      (value "MX Switch")
      (fields (field (name "BOM_Supplier Part") "Cherry MX or Alps/Matias switch"))
      (libsource (lib "") (part "MX Switch"))
    )
    (comp (ref "SW22")
      (value "MX Switch")
      (fields (field (name "BOM_Supplier Part") "Cherry MX or Alps/Matias switch"))
      (libsource (lib "") (part "MX Switch"))
    )
    (comp (ref "SW23")
      (value "MX Switch")
      (fields (field (name "BOM_Supplier Part") "Cherry MX or Alps/Matias switch"))
      (libsource (lib "") (part "MX Switch"))
    )
    (comp (ref "SW24")
      (value "MX Switch")
      (fields (field (name "BOM_Supplier Part") "Cherry MX or Alps/Matias switch"))
      (libsource (lib "") (part "MX Switch"))
    )
    (comp (ref "SW25")
      (value "MX Switch")
      (fields (field (name "BOM_Supplier Part") "Cherry MX or Alps/Matias switch"))
      (libsource (lib "") (part "MX Switch"))
    )
    (comp (ref "SW26")
      (value "MX Switch")
      (fields (field (name "BOM_Supplier Part") "Cherry MX or Alps/Matias switch"))
      (libsource (lib "") (part "MX Switch"))
    )
    (comp (ref "SW27")
      (value "MX Switch")
      (fields (field (name "BOM_Supplier Part") "Cherry MX or Alps/Matias switch"))
      (libsource (lib "") (part "MX Switch"))
    )
    (comp (ref "SW28")
      (value "MX Switch")
      (fields (field (name "BOM_Supplier Part") "Cherry MX or Alps/Matias switch"))
      (libsource (lib "") (part "MX Switch"))
    )
    (comp (ref "SW29")
      (value "MX Switch")
      (fields (field (name "BOM_Supplier Part") "Cherry MX or Alps/Matias switch"))
      (libsource (lib "") (part "MX Switch"))
    )
    (comp (ref "SW30")
      (value "MX Switch")
      (fields (field (name "BOM_Supplier Part") "Cherry MX or Alps/Matias switch"))
      (libsource (lib "") (part "MX Switch"))
    )
    (comp (ref "SW31")
      (value "MX Switch")
      (fields (field (name "BOM_Supplier Part") "Cherry MX or Alps/Matias switch"))
      (libsource (lib "") (part "MX Switch"))
    )
    (comp (ref "SW32")
      (value "MX Switch")
      (fields (field (name "BOM_Supplier Part") "Cherry MX or Alps/Matias switch"))
      (libsource (lib "") (part "MX Switch"))
    )
    (comp (ref "SW33")
      (value "MX Switch")
      (fields (field (name "BOM_Supplier Part") "Cherry MX or Alps/Matias switch"))
      (libsource (lib "") (part "MX Switch"))
    )
    (comp (ref "SW34")
      (value "MX Switch")
      (fields (field (name "BOM_Supplier Part") "Cherry MX or Alps/Matias switch"))
      (libsource (lib "") (part "MX Switch"))
    )
    (comp (ref "SW35")
      (value "MX Switch")
      (fields (field (name "BOM_Supplier Part") "Cherry MX or Alps/Matias switch"))
      (libsource (lib "") (part "MX Switch"))
    )
    (comp (ref "SW36")
      (value "MX Switch")
      (fields (field (name "BOM_Supplier Part") "Cherry MX or Alps/Matias switch"))
      (libsource (lib "") (part "MX Switch"))
    )
    (comp (ref "SW37")
      (value "MX Switch")
      (fields (field (name "BOM_Supplier Part") "Cherry MX or Alps/Matias switch"))
      (libsource (lib "") (part "MX Switch"))
    )
    (comp (ref "SW38")
      (value "MX Switch")
      (fields (field (name "BOM_Supplier Part") "Cherry MX or Alps/Matias switch"))
      (libsource (lib "") (part "MX Switch"))
    )
    (comp (ref "SW39")
      (value "MX Switch")
      (fields (field (name "BOM_Supplier Part") "Cherry MX or Alps/Matias switch"))
      (libsource (lib "") (part "MX Switch"))
    )
    (comp (ref "SW40")
      (value "MX Switch")
      (fields (field (name "BOM_Supplier Part") "Cherry MX or Alps/Matias switch"))
      (libsource (lib "") (part "MX Switch"))
    )
    (comp (ref "SW41")
      (value "MX Switch")
      (fields (field (name "BOM_Supplier Part") "Cherry MX or Alps/Matias switch"))
      (libsource (lib "") (part "MX Switch"))
    )
    (comp (ref "SW42")
      (value "MX Switch")
      (fields (field (name "BOM_Supplier Part") "Cherry MX or Alps/Matias switch"))
      (libsource (lib "") (part "MX Switch"))
    )
    (comp (ref "SW43")
      (value "MX Switch")
      (fields (field (name "BOM_Supplier Part") "Cherry MX or Alps/Matias switch"))
      (libsource (lib "") (part "MX Switch"))
    )
    (comp (ref "SW44")
      (value "MX Switch")
      (fields (field (name "BOM_Supplier Part") "Cherry MX or Alps/Matias switch"))
      (libsource (lib "") (part "MX Switch"))
    )
    (comp (ref "SW45")
      (value "MX Switch")
      (fields (field (name "BOM_Supplier Part") "Cherry MX or Alps/Matias switch"))
      (libsource (lib "") (part "MX Switch"))
    )
    (comp (ref "SW46")
      (value "MX Switch")
      (fields (field (name "BOM_Supplier Part") "Cherry MX or Alps/Matias switch"))
      (libsource (lib "") (part "MX Switch"))
    )
    (comp (ref "SW47")
      (value "MX Switch")
      (fields (field (name "BOM_Supplier Part") "Cherry MX or Alps/Matias switch"))
      (libsource (lib "") (part "MX Switch"))
    )
    (comp (ref "SW48")
      (value "MX Switch")
      (fields (field (name "BOM_Supplier Part") "Cherry MX or Alps/Matias switch"))
      (libsource (lib "") (part "MX Switch"))
    )
    (comp (ref "SW49")
      (value "MX Switch")
      (fields (field (name "BOM_Supplier Part") "Cherry MX or Alps/Matias switch"))
      (libsource (lib "") (part "MX Switch"))
    )
    (comp (ref "SW50")
      (value "MX Switch")
      (fields (field (name "BOM_Supplier Part") "Cherry MX or Alps/Matias switch"))
      (libsource (lib "") (part "MX Switch"))
    )
    (comp (ref "SW51")
      (value "MX Switch")
      (fields (field (name "BOM_Supplier Part") "Cherry MX or Alps/Matias switch"))
      (libsource (lib "") (part "MX Switch"))
    )
    (comp (ref "SW52")
      (value "MX Switch")
      (fields (field (name "BOM_Supplier Part") "Cherry MX or Alps/Matias switch"))
      (libsource (lib "") (part "MX Switch"))
    )
    (comp (ref "SW53")
      (value "MX Switch")
      (fields (field (name "BOM_Supplier Part") "Cherry MX or Alps/Matias switch"))
      (libsource (lib "") (part "MX Switch"))
    )
    (comp (ref "SW54")
      (value "MX Switch")
      (fields (field (name "BOM_Supplier Part") "Cherry MX or Alps/Matias switch"))
      (libsource (lib "") (part "MX Switch"))
    )
    (comp (ref "SW55")
      (value "MX Switch")
      (fields (field (name "BOM_Supplier Part") "Cherry MX or Alps/Matias switch"))
      (libsource (lib "") (part "MX Switch"))
    )
    (comp (ref "SW56")
      (value "MX Switch")
      (fields (field (name "BOM_Supplier Part") "Cherry MX or Alps/Matias switch"))
      (libsource (lib "") (part "MX Switch"))
    )
    (comp (ref "SW57")
      (value "MX Switch")
      (fields (field (name "BOM_Supplier Part") "Cherry MX or Alps/Matias switch"))
      (libsource (lib "") (part "MX Switch"))
    )
    (comp (ref "SW58")
      (value "MX Switch")
      (fields (field (name "BOM_Supplier Part") "Cherry MX or Alps/Matias switch"))
      (libsource (lib "") (part "MX Switch"))
    )
    (comp (ref "SW59")
      (value "MX Switch")
      (fields (field (name "BOM_Supplier Part") "Cherry MX or Alps/Matias switch"))
      (libsource (lib "") (part "MX Switch"))
    )
    (comp (ref "SW60")
      (value "MX Switch")
      (fields (field (name "BOM_Supplier Part") "Cherry MX or Alps/Matias switch"))
      (libsource (lib "") (part "MX Switch"))
    )
    (comp (ref "SW61")
      (value "MX Switch")
      (fields (field (name "BOM_Supplier Part") "Cherry MX or Alps/Matias switch"))
      (libsource (lib "") (part "MX Switch"))
    )
    (comp (ref "SW62")
      (value "MX Switch")
      (fields (field (name "BOM_Supplier Part") "Cherry MX or Alps/Matias switch"))
      (libsource (lib "") (part "MX Switch"))
    )
    (comp (ref "SW63")
      (value "MX Switch")
      (fields (field (name "BOM_Supplier Part") "Cherry MX or Alps/Matias switch"))
      (libsource (lib "") (part "MX Switch"))
    )
    (comp (ref "SW64")
      (value "MX Switch")
      (fields (field (name "BOM_Supplier Part") "Cherry MX or Alps/Matias switch"))
      (libsource (lib "") (part "MX Switch"))
    )
    (comp (ref "SW65")
      (value "MX Switch")
      (fields (field (name "BOM_Supplier Part") "Cherry MX or Alps/Matias switch"))
      (libsource (lib "") (part "MX Switch"))
    )
    (comp (ref "SW66")
      (value "MX Switch")
      (fields (field (name "BOM_Supplier Part") "Cherry MX or Alps/Matias switch"))
      (libsource (lib "") (part "MX Switch"))
    )
    (comp (ref "SW67")
      (value "MX Switch")
      (fields (field (name "BOM_Supplier Part") "Cherry MX or Alps/Matias switch"))
      (libsource (lib "") (part "MX Switch"))
    )
  )
  (nets
    (net (code "1") (name "BLED") (class "Default")
      (node (ref "SW1") (pin "3") (pinfunction "LED_3") (pintype "unspecified"))
      (node (ref "SW10") (pin "3") (pinfunction "LED_3") (pintype "unspecified"))
      (node (ref "SW11") (pin "3") (pinfunction "LED_3") (pintype "unspecified"))
      (node (ref "SW12") (pin "3") (pinfunction "LED_3") (pintype "unspecified"))
      (node (ref "SW13") (pin "3") (pinfunction "LED_3") (pintype "unspecified"))
      (node (ref "SW14") (pin "3") (pinfunction "LED_3") (pintype "unspecified"))
      (node (ref "SW15") (pin "3") (pinfunction "LED_3") (pintype "unspecified"))
      (node (ref "SW16") (pin "3") (pinfunction "LED_3") (pintype "unspecified"))
      (node (ref "SW17") (pin "3") (pinfunction "LED_3") (pintype "unspecified"))
      (node (ref "SW18") (pin "3") (pinfunction "LED_3") (pintype "unspecified"))
      (node (ref "SW19") (pin "3") (pinfunction "LED_3") (pintype "unspecified"))
      (node (ref "SW2") (pin "3") (pinfunction "LED_3") (pintype "unspecified"))
      (node (ref "SW20") (pin "3") (pinfunction "LED_3") (pintype "unspecified"))
      (node (ref "SW21") (pin "3") (pinfunction "LED_3") (pintype "unspecified"))
      (node (ref "SW22") (pin "3") (pinfunction "LED_3") (pintype "unspecified"))
      (node (ref "SW23") (pin "3") (pinfunction "LED_3") (pintype "unspecified"))
      (node (ref "SW24") (pin "3") (pinfunction "LED_3") (pintype "unspecified"))
      (node (ref "SW25") (pin "3") (pinfunction "LED_3") (pintype "unspecified"))
      (node (ref "SW26") (pin "3") (pinfunction "LED_3") (pintype "unspecified"))
      (node (ref "SW27") (pin "3") (pinfunction "LED_3") (pintype "unspecified"))
      (node (ref "SW28") (pin "3") (pinfunction "LED_3") (pintype "unspecified"))
      (node (ref "SW29") (pin "3") (pinfunction "LED_3") (pintype "unspecified"))
      (node (ref "SW3") (pin "3") (pinfunction "LED_3") (pintype "unspecified"))
      (node (ref "SW30") (pin "3") (pinfunction "LED_3") (pintype "unspecified"))
      (node (ref "SW31") (pin "3") (pinfunction "LED_3") (pintype "unspecified"))
      (node (ref "SW32") (pin "3") (pinfunction "LED_3") (pintype "unspecified"))
      (node (ref "SW33") (pin "3") (pinfunction "LED_3") (pintype "unspecified"))
      (node (ref "SW34") (pin "3") (pinfunction "LED_3") (pintype "unspecified"))
      (node (ref "SW35") (pin "3") (pinfunction "LED_3") (pintype "unspecified"))
      (node (ref "SW36") (pin "3") (pinfunction "LED_3") (pintype "unspecified"))
      (node (ref "SW37") (pin "3") (pinfunction "LED_3") (pintype "unspecified"))
      (node (ref "SW38") (pin "3") (pinfunction "LED_3") (pintype "unspecified"))
      (node (ref "SW39") (pin "3") (pinfunction "LED_3") (pintype "unspecified"))
      (node (ref "SW4") (pin "3") (pinfunction "LED_3") (pintype "unspecified"))
      (node (ref "SW40") (pin "3") (pinfunction "LED_3") (pintype "unspecified"))
      (node (ref "SW41") (pin "3") (pinfunction "LED_3") (pintype "unspecified"))
      (node (ref "SW42") (pin "3") (pinfunction "LED_3") (pintype "unspecified"))
      (node (ref "SW43") (pin "3") (pinfunction "LED_3") (pintype "unspecified"))
      (node (ref "SW44") (pin "3") (pinfunction "LED_3") (pintype "unspecified"))
      (node (ref "SW45") (pin "3") (pinfunction "LED_3") (pintype "unspecified"))
      (node (ref "SW46") (pin "3") (pinfunction "LED_3") (pintype "unspecified"))
      (node (ref "SW47") (pin "3") (pinfunction "LED_3") (pintype "unspecified"))
      (node (ref "SW48") (pin "3") (pinfunction "LED_3") (pintype "unspecified"))
      (node (ref "SW49") (pin "3") (pinfunction "LED_3") (pintype "unspecified"))
      (node (ref "SW5") (pin "3") (pinfunction "LED_3") (pintype "unspecified"))
      (node (ref "SW50") (pin "3") (pinfunction "LED_3") (pintype "unspecified"))
      (node (ref "SW51") (pin "3") (pinfunction "LED_3") (pintype "unspecified"))
      (node (ref "SW52") (pin "3") (pinfunction "LED_3") (pintype "unspecified"))
      (node (ref "SW53") (pin "3") (pinfunction "LED_3") (pintype "unspecified"))
      (node (ref "SW54") (pin "3") (pinfunction "LED_3") (pintype "unspecified"))
      (node (ref "SW55") (pin "3") (pinfunction "LED_3") (pintype "unspecified"))
      (node (ref "SW56") (pin "3") (pinfunction "LED_3") (pintype "unspecified"))
      (node (ref "SW57") (pin "3") (pinfunction "LED_3") (pintype "unspecified"))
      (node (ref "SW58") (pin "3") (pinfunction "LED_3") (pintype "unspecified"))
      (node (ref "SW59") (pin "3") (pinfunction "LED_3") (pintype "unspecified"))
      (node (ref "SW6") (pin "3") (pinfunction "LED_3") (pintype "unspecified"))
      (node (ref "SW60") (pin "3") (pinfunction "LED_3") (pintype "unspecified"))
      (node (ref "SW61") (pin "3") (pinfunction "LED_3") (pintype "unspecified"))
      (node (ref "SW62") (pin "3") (pinfunction "LED_3") (pintype "unspecified"))
      (node (ref "SW63") (pin "3") (pinfunction "LED_3") (pintype "unspecified"))
      (node (ref "SW64") (pin "3") (pinfunction "LED_3") (pintype "unspecified"))
      (node (ref "SW65") (pin "3") (pinfunction "LED_3") (pintype "unspecified"))
      (node (ref "SW66") (pin "3") (pinfunction "LED_3") (pintype "unspecified"))
      (node (ref "SW67") (pin "3") (pinfunction "LED_3") (pintype "unspecified"))
      (node (ref "SW69") (pin "1") (pinfunction "A1_1") (pintype "input"))
      (node (ref "SW7") (pin "3") (pinfunction "LED_3") (pintype "unspecified"))
      (node (ref "SW8") (pin "3") (pinfunction "LED_3") (pintype "unspecified"))
      (node (ref "SW9") (pin "3") (pinfunction "LED_3") (pintype "unspecified"))
    )
    (net (code "2") (name "Col0") (class "Default")
      (node (ref "SW1") (pin "1") (pinfunction "Col_1") (pintype "unspecified"))
      (node (ref "SW10") (pin "1") (pinfunction "Col_1") (pintype "unspecified"))
      (node (ref "SW11") (pin "1") (pinfunction "Col_1") (pintype "unspecified"))
      (node (ref "SW12") (pin "1") (pinfunction "Col_1") (pintype "unspecified"))
      (node (ref "SW13") (pin "1") (pinfunction "Col_1") (pintype "unspecified"))
      (node (ref "SW14") (pin "1") (pinfunction "Col_1") (pintype "unspecified"))
      (node (ref "SW15") (pin "1") (pinfunction "Col_1") (pintype "unspecified"))
      (node (ref "SW2") (pin "1") (pinfunction "Col_1") (pintype "unspecified"))
      (node (ref "SW3") (pin "1") (pinfunction "Col_1") (pintype "unspecified"))
      (node (ref "SW4") (pin "1") (pinfunction "Col_1") (pintype "unspecified"))
      (node (ref "SW5") (pin "1") (pinfunction "Col_1") (pintype "unspecified"))
      (node (ref "SW6") (pin "1") (pinfunction "Col_1") (pintype "unspecified"))
      (node (ref "SW7") (pin "1") (pinfunction "Col_1") (pintype "unspecified"))
      (node (ref "SW8") (pin "1") (pinfunction "Col_1") (pintype "unspecified"))
      (node (ref "SW9") (pin "1") (pinfunction "Col_1") (pintype "unspecified"))
      (node (ref "U1") (pin "8") (pinfunction "PB0(SS/PCINT0)_8") (pintype "unspecified"))
    )
    (net (code "3") (name "Col1") (class "Default")
      (node (ref "SW16") (pin "1") (pinfunction "Col_1") (pintype "unspecified"))
      (node (ref "SW17") (pin "1") (pinfunction "Col_1") (pintype "unspecified"))
      (node (ref "SW18") (pin "1") (pinfunction "Col_1") (pintype "unspecified"))
      (node (ref "SW19") (pin "1") (pinfunction "Col_1") (pintype "unspecified"))
      (node (ref "SW20") (pin "1") (pinfunction "Col_1") (pintype "unspecified"))
      (node (ref "SW21") (pin "1") (pinfunction "Col_1") (pintype "unspecified"))
      (node (ref "SW22") (pin "1") (pinfunction "Col_1") (pintype "unspecified"))
      (node (ref "SW23") (pin "1") (pinfunction "Col_1") (pintype "unspecified"))
      (node (ref "SW24") (pin "1") (pinfunction "Col_1") (pintype "unspecified"))
      (node (ref "SW25") (pin "1") (pinfunction "Col_1") (pintype "unspecified"))
      (node (ref "SW26") (pin "1") (pinfunction "Col_1") (pintype "unspecified"))
      (node (ref "SW27") (pin "1") (pinfunction "Col_1") (pintype "unspecified"))
      (node (ref "SW28") (pin "1") (pinfunction "Col_1") (pintype "unspecified"))
      (node (ref "SW29") (pin "1") (pinfunction "Col_1") (pintype "unspecified"))
      (node (ref "SW30") (pin "1") (pinfunction "Col_1") (pintype "unspecified"))
      (node (ref "U1") (pin "18") (pinfunction "PD0(OC0B/SCL/INT0)_18") (pintype "unspecified"))
    )
    (net (code "4") (name "Col2") (class "Default")
      (node (ref "SW31") (pin "1") (pinfunction "Col_1") (pintype "unspecified"))
      (node (ref "SW32") (pin "1") (pinfunction "Col_1") (pintype "unspecified"))
      (node (ref "SW33") (pin "1") (pinfunction "Col_1") (pintype "unspecified"))
      (node (ref "SW34") (pin "1") (pinfunction "Col_1") (pintype "unspecified"))
      (node (ref "SW35") (pin "1") (pinfunction "Col_1") (pintype "unspecified"))
      (node (ref "SW36") (pin "1") (pinfunction "Col_1") (pintype "unspecified"))
      (node (ref "SW37") (pin "1") (pinfunction "Col_1") (pintype "unspecified"))
      (node (ref "SW38") (pin "1") (pinfunction "Col_1") (pintype "unspecified"))
      (node (ref "SW39") (pin "1") (pinfunction "Col_1") (pintype "unspecified"))
      (node (ref "SW40") (pin "1") (pinfunction "Col_1") (pintype "unspecified"))
      (node (ref "SW41") (pin "1") (pinfunction "Col_1") (pintype "unspecified"))
      (node (ref "SW42") (pin "1") (pinfunction "Col_1") (pintype "unspecified"))
      (node (ref "U1") (pin "20") (pinfunction "PD2(RXD1/INT2)_20") (pintype "unspecified"))
    )
    (net (code "5") (name "Col3") (class "Default")
      (node (ref "SW43") (pin "1") (pinfunction "Col_1") (pintype "unspecified"))
      (node (ref "SW44") (pin "1") (pinfunction "Col_1") (pintype "unspecified"))
      (node (ref "SW45") (pin "1") (pinfunction "Col_1") (pintype "unspecified"))
      (node (ref "SW46") (pin "1") (pinfunction "Col_1") (pintype "unspecified"))
      (node (ref "SW47") (pin "1") (pinfunction "Col_1") (pintype "unspecified"))
      (node (ref "SW48") (pin "1") (pinfunction "Col_1") (pintype "unspecified"))
      (node (ref "SW49") (pin "1") (pinfunction "Col_1") (pintype "unspecified"))
      (node (ref "SW50") (pin "1") (pinfunction "Col_1") (pintype "unspecified"))
      (node (ref "SW51") (pin "1") (pinfunction "Col_1") (pintype "unspecified"))
      (node (ref "SW52") (pin "1") (pinfunction "Col_1") (pintype "unspecified"))
      (node (ref "U1") (pin "21") (pinfunction "PD3(TXD1/INT3)_21") (pintype "unspecified"))
    )
    (net (code "6") (name "Col4") (class "Default")
      (node (ref "SW53") (pin "1") (pinfunction "Col_1") (pintype "unspecified"))
      (node (ref "SW54") (pin "1") (pinfunction "Col_1") (pintype "unspecified"))
      (node (ref "SW55") (pin "1") (pinfunction "Col_1") (pintype "unspecified"))
      (node (ref "SW56") (pin "1") (pinfunction "Col_1") (pintype "unspecified"))
      (node (ref "SW57") (pin "1") (pinfunction "Col_1") (pintype "unspecified"))
      (node (ref "SW58") (pin "1") (pinfunction "Col_1") (pintype "unspecified"))
      (node (ref "SW59") (pin "1") (pinfunction "Col_1") (pintype "unspecified"))
      (node (ref "SW60") (pin "1") (pinfunction "Col_1") (pintype "unspecified"))
      (node (ref "SW61") (pin "1") (pinfunction "Col_1") (pintype "unspecified"))
      (node (ref "SW62") (pin "1") (pinfunction "Col_1") (pintype "unspecified"))
      (node (ref "U1") (pin "22") (pinfunction "PD5(XCK1/CTS#)_22") (pintype "unspecified"))
    )
    (net (code "7") (name "Col5") (class "Default")
      (node (ref "ENC1") (pin "E") (pinfunction "E_E") (pintype "unspecified"))
      (node (ref "ENC2") (pin "E") (pinfunction "E_E") (pintype "unspecified"))
      (node (ref "ENC3") (pin "E") (pinfunction "E_E") (pintype "unspecified"))
      (node (ref "ENC4") (pin "E") (pinfunction "E_E") (pintype "unspecified"))
      (node (ref "ENC5") (pin "E") (pinfunction "E_E") (pintype "unspecified"))
      (node (ref "SW63") (pin "1") (pinfunction "Col_1") (pintype "unspecified"))
      (node (ref "SW64") (pin "1") (pinfunction "Col_1") (pintype "unspecified"))
      (node (ref "SW65") (pin "1") (pinfunction "Col_1") (pintype "unspecified"))
      (node (ref "SW66") (pin "1") (pinfunction "Col_1") (pintype "unspecified"))
      (node (ref "SW67") (pin "1") (pinfunction "Col_1") (pintype "unspecified"))
      (node (ref "U1") (pin "28") (pinfunction "PB4(PCINT4/ADC11)_28") (pintype "unspecified"))
    )
    (net (code "8") (name "Din_N") (class "Default")
      (node (ref "ESD1") (pin "3") (pinfunction "I/O2_3") (pintype "unspecified"))
      (node (ref "USBC1") (pin "A7") (pinfunction "DN1_A7") (pintype "unspecified"))
      (node (ref "USBC1") (pin "B7") (pinfunction "DN2_B7") (pintype "unspecified"))
    )
    (net (code "9") (name "Din_P") (class "Default")
      (node (ref "ESD1") (pin "1") (pinfunction "I/O1_1") (pintype "unspecified"))
      (node (ref "USBC1") (pin "A6") (pinfunction "DP1_A6") (pintype "unspecified"))
      (node (ref "USBC1") (pin "B6") (pinfunction "DP2_B6") (pintype "unspecified"))
    )
    (net (code "10") (name "Dout_N") (class "Default")
      (node (ref "ESD1") (pin "4") (pinfunction "I/O2_4") (pintype "unspecified"))
      (node (ref "R20") (pin "2") (pinfunction "2_2") (pintype "input"))
    )
    (net (code "11") (name "Dout_P") (class "Default")
      (node (ref "ESD1") (pin "6") (pinfunction "I/O1_6") (pintype "unspecified"))
      (node (ref "R21") (pin "2") (pinfunction "2_2") (pintype "input"))
    )
    (net (code "12") (name "GND") (class "Default")
      (node (ref "C1") (pin "2") (pinfunction "2_2") (pintype "unspecified"))
      (node (ref "C10") (pin "1") (pinfunction "1_1") (pintype "unspecified"))
      (node (ref "C11") (pin "1") (pinfunction "1_1") (pintype "input"))
      (node (ref "C12") (pin "1") (pinfunction "1_1") (pintype "input"))
      (node (ref "C13") (pin "1") (pinfunction "1_1") (pintype "input"))
      (node (ref "C14") (pin "2") (pinfunction "2_2") (pintype "unspecified"))
      (node (ref "C15") (pin "1") (pinfunction "1_1") (pintype "input"))
      (node (ref "C16") (pin "1") (pinfunction "1_1") (pintype "unspecified"))
      (node (ref "C17") (pin "1") (pinfunction "1_1") (pintype "unspecified"))
      (node (ref "C18") (pin "1") (pinfunction "1_1") (pintype "unspecified"))
      (node (ref "C19") (pin "1") (pinfunction "1_1") (pintype "unspecified"))
      (node (ref "C2") (pin "1") (pinfunction "1_1") (pintype "unspecified"))
      (node (ref "C20") (pin "1") (pinfunction "1_1") (pintype "unspecified"))
      (node (ref "C3") (pin "2") (pinfunction "2_2") (pintype "unspecified"))
      (node (ref "C4") (pin "1") (pinfunction "1_1") (pintype "unspecified"))
      (node (ref "C5") (pin "2") (pinfunction "2_2") (pintype "unspecified"))
      (node (ref "C6") (pin "1") (pinfunction "1_1") (pintype "unspecified"))
      (node (ref "C7") (pin "2") (pinfunction "2_2") (pintype "unspecified"))
      (node (ref "C8") (pin "1") (pinfunction "1_1") (pintype "unspecified"))
      (node (ref "C9") (pin "2") (pinfunction "2_2") (pintype "unspecified"))
      (node (ref "ENC1") (pin "C") (pinfunction "C_C") (pintype "unspecified"))
      (node (ref "ENC2") (pin "C") (pinfunction "C_C") (pintype "unspecified"))
      (node (ref "ENC3") (pin "C") (pinfunction "C_C") (pintype "unspecified"))
      (node (ref "ENC4") (pin "C") (pinfunction "C_C") (pintype "unspecified"))
      (node (ref "ENC5") (pin "C") (pinfunction "C_C") (pintype "unspecified"))
      (node (ref "ESD1") (pin "2") (pinfunction "GND_2") (pintype "unspecified"))
      (node (ref "OLED1") (pin "4") (pinfunction "GND_4") (pintype "unspecified"))
      (node (ref "R1") (pin "1") (pinfunction "1_1") (pintype "unspecified"))
      (node (ref "R10") (pin "1") (pinfunction "1_1") (pintype "unspecified"))
      (node (ref "R11") (pin "1") (pinfunction "1_1") (pintype "unspecified"))
      (node (ref "R12") (pin "1") (pinfunction "1_1") (pintype "unspecified"))
      (node (ref "R13") (pin "1") (pinfunction "1_1") (pintype "unspecified"))
      (node (ref "R14") (pin "1") (pinfunction "1_1") (pintype "unspecified"))
      (node (ref "R2") (pin "1") (pinfunction "1_1") (pintype "unspecified"))
      (node (ref "R22") (pin "1") (pinfunction "1_1") (pintype "unspecified"))
      (node (ref "R23") (pin "1") (pinfunction "1_1") (pintype "input"))
      (node (ref "R24") (pin "2") (pinfunction "2_2") (pintype "unspecified"))
      (node (ref "R25") (pin "1") (pinfunction "1_1") (pintype "unspecified"))
      (node (ref "R3") (pin "1") (pinfunction "1_1") (pintype "unspecified"))
      (node (ref "R5") (pin "1") (pinfunction "1_1") (pintype "unspecified"))
      (node (ref "R6") (pin "1") (pinfunction "1_1") (pintype "unspecified"))
      (node (ref "R7") (pin "1") (pinfunction "1_1") (pintype "unspecified"))
      (node (ref "R8") (pin "1") (pinfunction "1_1") (pintype "unspecified"))
      (node (ref "R9") (pin "1") (pinfunction "1_1") (pintype "unspecified"))
      (node (ref "STO1") (pin "1") (pinfunction "Standoff_1") (pintype "unspecified"))
      (node (ref "STO2") (pin "1") (pinfunction "Standoff_1") (pintype "unspecified"))
      (node (ref "STO3") (pin "1") (pinfunction "Standoff_1") (pintype "unspecified"))
      (node (ref "STO4") (pin "1") (pinfunction "Standoff_1") (pintype "unspecified"))
      (node (ref "STO5") (pin "1") (pinfunction "Standoff_1") (pintype "unspecified"))
      (node (ref "STO6") (pin "1") (pinfunction "Standoff_1") (pintype "unspecified"))
      (node (ref "STO7") (pin "1") (pinfunction "Standoff_1") (pintype "unspecified"))
      (node (ref "SW68") (pin "3") (pinfunction "C_3") (pintype "unspecified"))
      (node (ref "SW68") (pin "4") (pinfunction "D_4") (pintype "unspecified"))
      (node (ref "SW69") (pin "2") (pinfunction "A2_2") (pintype "input"))
      (node (ref "U1") (pin "15") (pinfunction "GND_15") (pintype "unspecified"))
      (node (ref "U1") (pin "23") (pinfunction "GND_23") (pintype "unspecified"))
      (node (ref "U1") (pin "35") (pinfunction "GND_35") (pintype "unspecified"))
      (node (ref "U1") (pin "43") (pinfunction "GND_43") (pintype "unspecified"))
      (node (ref "U1") (pin "45") (pinfunction "EP_45") (pintype "unspecified"))
      (node (ref "U1") (pin "5") (pinfunction "UGnd_5") (pintype "unspecified"))
      (node (ref "U2") (pin "4") (pinfunction "._4") (pintype "unspecified"))
      (node (ref "USBC1") (pin "A1") (pinfunction "GND_A1") (pintype "unspecified"))
      (node (ref "USBC1") (pin "A12") (pinfunction "GND_A12") (pintype "unspecified"))
      (node (ref "X1") (pin "2") (pinfunction "GND_2") (pintype "unspecified"))
      (node (ref "X1") (pin "4") (pinfunction "GND_4") (pintype "unspecified"))
    )
    (net (code "13") (name "MISO") (class "Default")
      (node (ref "HEADER") (pin "4") (pinfunction "MISO_4") (pintype "unspecified"))
      (node (ref "U1") (pin "11") (pinfunction "PB3(PDO/PCINT3/MISO)_11") (pintype "unspecified"))
      (node (ref "U3") (pin "4") (pinfunction "._4") (pintype "unspecified"))
    )
    (net (code "14") (name "MOSI") (class "Default")
      (node (ref "HEADER") (pin "3") (pinfunction "MOSI_3") (pintype "unspecified"))
      (node (ref "U1") (pin "10") (pinfunction "PB2(PDI/PCINT2/MOSI)_10") (pintype "unspecified"))
      (node (ref "U3") (pin "3") (pinfunction "._3") (pintype "unspecified"))
    )
    (net (code "15") (name "Net-(D1-A)") (class "Default")
      (node (ref "D1") (pin "2") (pinfunction "A_2") (pintype "unspecified"))
      (node (ref "SW1") (pin "2") (pinfunction "Row_2") (pintype "unspecified"))
    )
    (net (code "16") (name "Net-(D2-A)") (class "Default")
      (node (ref "D2") (pin "2") (pinfunction "A_2") (pintype "unspecified"))
      (node (ref "SW2") (pin "2") (pinfunction "Row_2") (pintype "unspecified"))
    )
    (net (code "17") (name "Net-(D3-A)") (class "Default")
      (node (ref "D3") (pin "2") (pinfunction "A_2") (pintype "unspecified"))
      (node (ref "SW3") (pin "2") (pinfunction "Row_2") (pintype "unspecified"))
    )
    (net (code "18") (name "Net-(D4-A)") (class "Default")
      (node (ref "D4") (pin "2") (pinfunction "A_2") (pintype "unspecified"))
      (node (ref "SW4") (pin "2") (pinfunction "Row_2") (pintype "unspecified"))
    )
    (net (code "19") (name "Net-(D5-A)") (class "Default")
      (node (ref "D5") (pin "2") (pinfunction "A_2") (pintype "unspecified"))
      (node (ref "SW5") (pin "2") (pinfunction "Row_2") (pintype "unspecified"))
    )
    (net (code "20") (name "Net-(D6-A)") (class "Default")
      (node (ref "D6") (pin "2") (pinfunction "A_2") (pintype "unspecified"))
      (node (ref "SW6") (pin "2") (pinfunction "Row_2") (pintype "unspecified"))
    )
    (net (code "21") (name "Net-(D7-A)") (class "Default")
      (node (ref "D7") (pin "2") (pinfunction "A_2") (pintype "unspecified"))
      (node (ref "SW7") (pin "2") (pinfunction "Row_2") (pintype "unspecified"))
    )
    (net (code "22") (name "Net-(D8-A)") (class "Default")
      (node (ref "D8") (pin "2") (pinfunction "A_2") (pintype "unspecified"))
      (node (ref "SW8") (pin "2") (pinfunction "Row_2") (pintype "unspecified"))
    )
    (net (code "23") (name "Net-(D9-A)") (class "Default")
      (node (ref "D9") (pin "2") (pinfunction "A_2") (pintype "unspecified"))
      (node (ref "SW9") (pin "2") (pinfunction "Row_2") (pintype "unspecified"))
    )
    (net (code "24") (name "Net-(D10-A)") (class "Default")
      (node (ref "D10") (pin "2") (pinfunction "A_2") (pintype "unspecified"))
      (node (ref "SW10") (pin "2") (pinfunction "Row_2") (pintype "unspecified"))
    )
    (net (code "25") (name "Net-(D11-A)") (class "Default")
      (node (ref "D11") (pin "2") (pinfunction "A_2") (pintype "unspecified"))
      (node (ref "SW11") (pin "2") (pinfunction "Row_2") (pintype "unspecified"))
    )
    (net (code "26") (name "Net-(D12-A)") (class "Default")
      (node (ref "D12") (pin "2") (pinfunction "A_2") (pintype "unspecified"))
      (node (ref "SW12") (pin "2") (pinfunction "Row_2") (pintype "unspecified"))
    )
    (net (code "27") (name "Net-(D13-A)") (class "Default")
      (node (ref "D13") (pin "2") (pinfunction "A_2") (pintype "unspecified"))
      (node (ref "SW13") (pin "2") (pinfunction "Row_2") (pintype "unspecified"))
    )
    (net (code "28") (name "Net-(D14-A)") (class "Default")
      (node (ref "D14") (pin "2") (pinfunction "A_2") (pintype "unspecified"))
      (node (ref "SW14") (pin "2") (pinfunction "Row_2") (pintype "unspecified"))
    )
    (net (code "29") (name "Net-(D15-A)") (class "Default")
      (node (ref "D15") (pin "2") (pinfunction "A_2") (pintype "unspecified"))
      (node (ref "SW15") (pin "2") (pinfunction "Row_2") (pintype "unspecified"))
    )
    (net (code "30") (name "Net-(D16-A)") (class "Default")
      (node (ref "D16") (pin "2") (pinfunction "A_2") (pintype "unspecified"))
      (node (ref "SW16") (pin "2") (pinfunction "Row_2") (pintype "unspecified"))
    )
    (net (code "31") (name "Net-(D17-A)") (class "Default")
      (node (ref "D17") (pin "2") (pinfunction "A_2") (pintype "unspecified"))
      (node (ref "SW17") (pin "2") (pinfunction "Row_2") (pintype "unspecified"))
    )
    (net (code "32") (name "Net-(D18-A)") (class "Default")
      (node (ref "D18") (pin "2") (pinfunction "A_2") (pintype "unspecified"))
      (node (ref "SW18") (pin "2") (pinfunction "Row_2") (pintype "unspecified"))
    )
    (net (code "33") (name "Net-(D19-A)") (class "Default")
      (node (ref "D19") (pin "2") (pinfunction "A_2") (pintype "unspecified"))
      (node (ref "SW19") (pin "2") (pinfunction "Row_2") (pintype "unspecified"))
    )
    (net (code "34") (name "Net-(D20-A)") (class "Default")
      (node (ref "D20") (pin "2") (pinfunction "A_2") (pintype "unspecified"))
      (node (ref "SW20") (pin "2") (pinfunction "Row_2") (pintype "unspecified"))
    )
    (net (code "35") (name "Net-(D21-A)") (class "Default")
      (node (ref "D21") (pin "2") (pinfunction "A_2") (pintype "unspecified"))
      (node (ref "SW21") (pin "2") (pinfunction "Row_2") (pintype "unspecified"))
    )
    (net (code "36") (name "Net-(D22-A)") (class "Default")
      (node (ref "D22") (pin "2") (pinfunction "A_2") (pintype "unspecified"))
      (node (ref "SW22") (pin "2") (pinfunction "Row_2") (pintype "unspecified"))
    )
    (net (code "37") (name "Net-(D23-A)") (class "Default")
      (node (ref "D23") (pin "2") (pinfunction "A_2") (pintype "unspecified"))
      (node (ref "SW23") (pin "2") (pinfunction "Row_2") (pintype "unspecified"))
    )
    (net (code "38") (name "Net-(D24-A)") (class "Default")
      (node (ref "D24") (pin "2") (pinfunction "A_2") (pintype "unspecified"))
      (node (ref "SW24") (pin "2") (pinfunction "Row_2") (pintype "unspecified"))
    )
    (net (code "39") (name "Net-(D25-A)") (class "Default")
      (node (ref "D25") (pin "2") (pinfunction "A_2") (pintype "unspecified"))
      (node (ref "SW25") (pin "2") (pinfunction "Row_2") (pintype "unspecified"))
    )
    (net (code "40") (name "Net-(D26-A)") (class "Default")
      (node (ref "D26") (pin "2") (pinfunction "A_2") (pintype "unspecified"))
      (node (ref "SW26") (pin "2") (pinfunction "Row_2") (pintype "unspecified"))
    )
    (net (code "41") (name "Net-(D27-A)") (class "Default")
      (node (ref "D27") (pin "2") (pinfunction "A_2") (pintype "unspecified"))
      (node (ref "SW27") (pin "2") (pinfunction "Row_2") (pintype "unspecified"))
    )
    (net (code "42") (name "Net-(D28-A)") (class "Default")
      (node (ref "D28") (pin "2") (pinfunction "A_2") (pintype "unspecified"))
      (node (ref "SW28") (pin "2") (pinfunction "Row_2") (pintype "unspecified"))
    )
    (net (code "43") (name "Net-(D29-A)") (class "Default")
      (node (ref "D29") (pin "2") (pinfunction "A_2") (pintype "unspecified"))
      (node (ref "SW29") (pin "2") (pinfunction "Row_2") (pintype "unspecified"))
    )
    (net (code "44") (name "Net-(D30-A)") (class "Default")
      (node (ref "D30") (pin "2") (pinfunction "A_2") (pintype "unspecified"))
      (node (ref "SW30") (pin "2") (pinfunction "Row_2") (pintype "unspecified"))
    )
    (net (code "45") (name "Net-(D31-A)") (class "Default")
      (node (ref "D31") (pin "2") (pinfunction "A_2") (pintype "unspecified"))
      (node (ref "SW31") (pin "2") (pinfunction "Row_2") (pintype "unspecified"))
    )
    (net (code "46") (name "Net-(D32-A)") (class "Default")
      (node (ref "D32") (pin "2") (pinfunction "A_2") (pintype "unspecified"))
      (node (ref "SW32") (pin "2") (pinfunction "Row_2") (pintype "unspecified"))
    )
    (net (code "47") (name "Net-(D33-A)") (class "Default")
      (node (ref "D33") (pin "2") (pinfunction "A_2") (pintype "unspecified"))
      (node (ref "SW33") (pin "2") (pinfunction "Row_2") (pintype "unspecified"))
    )
    (net (code "48") (name "Net-(D34-A)") (class "Default")
      (node (ref "D34") (pin "2") (pinfunction "A_2") (pintype "unspecified"))
      (node (ref "SW34") (pin "2") (pinfunction "Row_2") (pintype "unspecified"))
      (node (ref "SW35") (pin "2") (pinfunction "Row_2") (pintype "unspecified"))
    )
    (net (code "49") (name "Net-(D35-A)") (class "Default")
      (node (ref "D35") (pin "2") (pinfunction "A_2") (pintype "unspecified"))
      (node (ref "SW36") (pin "2") (pinfunction "Row_2") (pintype "unspecified"))
      (node (ref "SW37") (pin "2") (pinfunction "Row_2") (pintype "unspecified"))
    )
    (net (code "50") (name "Net-(D36-A)") (class "Default")
      (node (ref "D36") (pin "2") (pinfunction "A_2") (pintype "unspecified"))
      (node (ref "SW38") (pin "2") (pinfunction "Row_2") (pintype "unspecified"))
    )
    (net (code "51") (name "Net-(D37-A)") (class "Default")
      (node (ref "D37") (pin "2") (pinfunction "A_2") (pintype "unspecified"))
      (node (ref "SW39") (pin "2") (pinfunction "Row_2") (pintype "unspecified"))
    )
    (net (code "52") (name "Net-(D38-A)") (class "Default")
      (node (ref "D38") (pin "2") (pinfunction "A_2") (pintype "unspecified"))
      (node (ref "SW40") (pin "2") (pinfunction "Row_2") (pintype "unspecified"))
    )
    (net (code "53") (name "Net-(D39-A)") (class "Default")
      (node (ref "D39") (pin "2") (pinfunction "A_2") (pintype "unspecified"))
      (node (ref "SW41") (pin "2") (pinfunction "Row_2") (pintype "unspecified"))
    )
    (net (code "54") (name "Net-(D40-A)") (class "Default")
      (node (ref "D40") (pin "2") (pinfunction "A_2") (pintype "unspecified"))
      (node (ref "SW42") (pin "2") (pinfunction "Row_2") (pintype "unspecified"))
    )
    (net (code "55") (name "Net-(D41-A)") (class "Default")
      (node (ref "D41") (pin "2") (pinfunction "A_2") (pintype "unspecified"))
      (node (ref "SW43") (pin "2") (pinfunction "Row_2") (pintype "unspecified"))
    )
    (net (code "56") (name "Net-(D42-A)") (class "Default")
      (node (ref "D42") (pin "2") (pinfunction "A_2") (pintype "unspecified"))
      (node (ref "SW44") (pin "2") (pinfunction "Row_2") (pintype "unspecified"))
    )
    (net (code "57") (name "Net-(D43-A)") (class "Default")
      (node (ref "D43") (pin "2") (pinfunction "A_2") (pintype "unspecified"))
      (node (ref "SW45") (pin "2") (pinfunction "Row_2") (pintype "unspecified"))
    )
    (net (code "58") (name "Net-(D44-A)") (class "Default")
      (node (ref "D44") (pin "2") (pinfunction "A_2") (pintype "unspecified"))
      (node (ref "SW46") (pin "2") (pinfunction "Row_2") (pintype "unspecified"))
    )
    (net (code "59") (name "Net-(D45-A)") (class "Default")
      (node (ref "D45") (pin "2") (pinfunction "A_2") (pintype "unspecified"))
      (node (ref "SW47") (pin "2") (pinfunction "Row_2") (pintype "unspecified"))
    )
    (net (code "60") (name "Net-(D46-A)") (class "Default")
      (node (ref "D46") (pin "2") (pinfunction "A_2") (pintype "unspecified"))
      (node (ref "SW48") (pin "2") (pinfunction "Row_2") (pintype "unspecified"))
    )
    (net (code "61") (name "Net-(D47-A)") (class "Default")
      (node (ref "D47") (pin "2") (pinfunction "A_2") (pintype "unspecified"))
      (node (ref "SW49") (pin "2") (pinfunction "Row_2") (pintype "unspecified"))
    )
    (net (code "62") (name "Net-(D48-A)") (class "Default")
      (node (ref "D48") (pin "2") (pinfunction "A_2") (pintype "unspecified"))
      (node (ref "SW50") (pin "2") (pinfunction "Row_2") (pintype "unspecified"))
    )
    (net (code "63") (name "Net-(D49-A)") (class "Default")
      (node (ref "D49") (pin "2") (pinfunction "A_2") (pintype "unspecified"))
      (node (ref "SW51") (pin "2") (pinfunction "Row_2") (pintype "unspecified"))
    )
    (net (code "64") (name "Net-(D50-A)") (class "Default")
      (node (ref "D50") (pin "2") (pinfunction "A_2") (pintype "unspecified"))
      (node (ref "SW52") (pin "2") (pinfunction "Row_2") (pintype "unspecified"))
    )
    (net (code "65") (name "Net-(D51-A)") (class "Default")
      (node (ref "D51") (pin "2") (pinfunction "A_2") (pintype "unspecified"))
      (node (ref "SW53") (pin "2") (pinfunction "Row_2") (pintype "unspecified"))
    )
    (net (code "66") (name "Net-(D52-A)") (class "Default")
      (node (ref "D52") (pin "2") (pinfunction "A_2") (pintype "unspecified"))
      (node (ref "SW54") (pin "2") (pinfunction "Row_2") (pintype "unspecified"))
    )
    (net (code "67") (name "Net-(D53-A)") (class "Default")
      (node (ref "D53") (pin "2") (pinfunction "A_2") (pintype "unspecified"))
      (node (ref "SW55") (pin "2") (pinfunction "Row_2") (pintype "unspecified"))
    )
    (net (code "68") (name "Net-(D54-A)") (class "Default")
      (node (ref "D54") (pin "2") (pinfunction "A_2") (pintype "unspecified"))
      (node (ref "SW56") (pin "2") (pinfunction "Row_2") (pintype "unspecified"))
    )
    (net (code "69") (name "Net-(D55-A)") (class "Default")
      (node (ref "D55") (pin "2") (pinfunction "A_2") (pintype "unspecified"))
      (node (ref "SW57") (pin "2") (pinfunction "Row_2") (pintype "unspecified"))
    )
    (net (code "70") (name "Net-(D56-A)") (class "Default")
      (node (ref "D56") (pin "2") (pinfunction "A_2") (pintype "unspecified"))
      (node (ref "SW58") (pin "2") (pinfunction "Row_2") (pintype "unspecified"))
    )
    (net (code "71") (name "Net-(D57-A)") (class "Default")
      (node (ref "D57") (pin "2") (pinfunction "A_2") (pintype "unspecified"))
      (node (ref "SW59") (pin "2") (pinfunction "Row_2") (pintype "unspecified"))
    )
    (net (code "72") (name "Net-(D58-A)") (class "Default")
      (node (ref "D58") (pin "2") (pinfunction "A_2") (pintype "unspecified"))
      (node (ref "SW60") (pin "2") (pinfunction "Row_2") (pintype "unspecified"))
    )
    (net (code "73") (name "Net-(D59-A)") (class "Default")
      (node (ref "D59") (pin "2") (pinfunction "A_2") (pintype "unspecified"))
      (node (ref "SW61") (pin "2") (pinfunction "Row_2") (pintype "unspecified"))
    )
    (net (code "74") (name "Net-(D60-A)") (class "Default")
      (node (ref "D60") (pin "2") (pinfunction "A_2") (pintype "unspecified"))
      (node (ref "SW62") (pin "2") (pinfunction "Row_2") (pintype "unspecified"))
    )
    (net (code "75") (name "Net-(D61-A)") (class "Default")
      (node (ref "D61") (pin "2") (pinfunction "A_2") (pintype "unspecified"))
      (node (ref "SW63") (pin "2") (pinfunction "Row_2") (pintype "unspecified"))
    )
    (net (code "76") (name "Net-(D62-A)") (class "Default")
      (node (ref "D62") (pin "2") (pinfunction "A_2") (pintype "unspecified"))
      (node (ref "SW64") (pin "2") (pinfunction "Row_2") (pintype "unspecified"))
    )
    (net (code "77") (name "Net-(D63-A)") (class "Default")
      (node (ref "D63") (pin "2") (pinfunction "A_2") (pintype "unspecified"))
      (node (ref "SW65") (pin "2") (pinfunction "Row_2") (pintype "unspecified"))
    )
    (net (code "78") (name "Net-(D64-A)") (class "Default")
      (node (ref "D64") (pin "2") (pinfunction "A_2") (pintype "unspecified"))
      (node (ref "SW66") (pin "2") (pinfunction "Row_2") (pintype "unspecified"))
    )
    (net (code "79") (name "Net-(D65-A)") (class "Default")
      (node (ref "D65") (pin "2") (pinfunction "A_2") (pintype "unspecified"))
      (node (ref "SW67") (pin "2") (pinfunction "Row_2") (pintype "unspecified"))
    )
    (net (code "80") (name "Net-(D66-A)") (class "Default")
      (node (ref "D66") (pin "2") (pinfunction "A_2") (pintype "unspecified"))
      (node (ref "ENC2") (pin "D") (pinfunction "D_D") (pintype "unspecified"))
    )
    (net (code "81") (name "Net-(D67-A)") (class "Default")
      (node (ref "D67") (pin "2") (pinfunction "A_2") (pintype "unspecified"))
      (node (ref "ENC3") (pin "D") (pinfunction "D_D") (pintype "unspecified"))
    )
    (net (code "82") (name "Net-(D68-A)") (class "Default")
      (node (ref "D68") (pin "2") (pinfunction "A_2") (pintype "unspecified"))
      (node (ref "ENC4") (pin "D") (pinfunction "D_D") (pintype "unspecified"))
    )
    (net (code "83") (name "Net-(D69-A)") (class "Default")
      (node (ref "D69") (pin "2") (pinfunction "A_2") (pintype "unspecified"))
      (node (ref "ENC5") (pin "D") (pinfunction "D_D") (pintype "unspecified"))
    )
    (net (code "84") (name "Net-(D70-A)") (class "Default")
      (node (ref "D70") (pin "2") (pinfunction "A_2") (pintype "unspecified"))
      (node (ref "ENC1") (pin "D") (pinfunction "D_D") (pintype "unspecified"))
    )
    (net (code "85") (name "Net-(PWR1-K)") (class "Default")
      (node (ref "PWR1") (pin "2") (pinfunction "K_2") (pintype "unspecified"))
      (node (ref "R25") (pin "2") (pinfunction "2_2") (pintype "unspecified"))
    )
    (net (code "86") (name "Net-(SW1-GND-LED)") (class "Default")
      (node (ref "R1") (pin "2") (pinfunction "2_2") (pintype "unspecified"))
      (node (ref "SW1") (pin "4") (pinfunction "GND-LED_4") (pintype "unspecified"))
      (node (ref "SW2") (pin "4") (pinfunction "GND-LED_4") (pintype "unspecified"))
      (node (ref "SW3") (pin "4") (pinfunction "GND-LED_4") (pintype "unspecified"))
      (node (ref "SW4") (pin "4") (pinfunction "GND-LED_4") (pintype "unspecified"))
      (node (ref "SW5") (pin "4") (pinfunction "GND-LED_4") (pintype "unspecified"))
    )
    (net (code "87") (name "Net-(SW10-GND-LED)") (class "Default")
      (node (ref "R2") (pin "2") (pinfunction "2_2") (pintype "unspecified"))
      (node (ref "SW10") (pin "4") (pinfunction "GND-LED_4") (pintype "unspecified"))
      (node (ref "SW6") (pin "4") (pinfunction "GND-LED_4") (pintype "unspecified"))
      (node (ref "SW7") (pin "4") (pinfunction "GND-LED_4") (pintype "unspecified"))
      (node (ref "SW8") (pin "4") (pinfunction "GND-LED_4") (pintype "unspecified"))
      (node (ref "SW9") (pin "4") (pinfunction "GND-LED_4") (pintype "unspecified"))
    )
    (net (code "88") (name "Net-(SW11-GND-LED)") (class "Default")
      (node (ref "R3") (pin "2") (pinfunction "2_2") (pintype "unspecified"))
      (node (ref "SW11") (pin "4") (pinfunction "GND-LED_4") (pintype "unspecified"))
      (node (ref "SW12") (pin "4") (pinfunction "GND-LED_4") (pintype "unspecified"))
      (node (ref "SW13") (pin "4") (pinfunction "GND-LED_4") (pintype "unspecified"))
      (node (ref "SW14") (pin "4") (pinfunction "GND-LED_4") (pintype "unspecified"))
      (node (ref "SW15") (pin "4") (pinfunction "GND-LED_4") (pintype "unspecified"))
    )
    (net (code "89") (name "Net-(SW16-GND-LED)") (class "Default")
      (node (ref "R5") (pin "2") (pinfunction "2_2") (pintype "unspecified"))
      (node (ref "SW16") (pin "4") (pinfunction "GND-LED_4") (pintype "unspecified"))
      (node (ref "SW17") (pin "4") (pinfunction "GND-LED_4") (pintype "unspecified"))
      (node (ref "SW18") (pin "4") (pinfunction "GND-LED_4") (pintype "unspecified"))
      (node (ref "SW19") (pin "4") (pinfunction "GND-LED_4") (pintype "unspecified"))
      (node (ref "SW20") (pin "4") (pinfunction "GND-LED_4") (pintype "unspecified"))
    )
    (net (code "90") (name "Net-(SW21-GND-LED)") (class "Default")
      (node (ref "R6") (pin "2") (pinfunction "2_2") (pintype "unspecified"))
      (node (ref "SW21") (pin "4") (pinfunction "GND-LED_4") (pintype "unspecified"))
      (node (ref "SW22") (pin "4") (pinfunction "GND-LED_4") (pintype "unspecified"))
      (node (ref "SW23") (pin "4") (pinfunction "GND-LED_4") (pintype "unspecified"))
      (node (ref "SW24") (pin "4") (pinfunction "GND-LED_4") (pintype "unspecified"))
      (node (ref "SW25") (pin "4") (pinfunction "GND-LED_4") (pintype "unspecified"))
    )
    (net (code "91") (name "Net-(SW26-GND-LED)") (class "Default")
      (node (ref "R7") (pin "2") (pinfunction "2_2") (pintype "unspecified"))
      (node (ref "SW26") (pin "4") (pinfunction "GND-LED_4") (pintype "unspecified"))
      (node (ref "SW27") (pin "4") (pinfunction "GND-LED_4") (pintype "unspecified"))
      (node (ref "SW28") (pin "4") (pinfunction "GND-LED_4") (pintype "unspecified"))
      (node (ref "SW29") (pin "4") (pinfunction "GND-LED_4") (pintype "unspecified"))
      (node (ref "SW30") (pin "4") (pinfunction "GND-LED_4") (pintype "unspecified"))
    )
    (net (code "92") (name "Net-(SW31-GND-LED)") (class "Default")
      (node (ref "R8") (pin "2") (pinfunction "2_2") (pintype "unspecified"))
      (node (ref "SW31") (pin "4") (pinfunction "GND-LED_4") (pintype "unspecified"))
      (node (ref "SW32") (pin "4") (pinfunction "GND-LED_4") (pintype "unspecified"))
      (node (ref "SW33") (pin "4") (pinfunction "GND-LED_4") (pintype "unspecified"))
      (node (ref "SW34") (pin "4") (pinfunction "GND-LED_4") (pintype "unspecified"))
      (node (ref "SW35") (pin "4") (pinfunction "GND-LED_4") (pintype "unspecified"))
      (node (ref "SW36") (pin "4") (pinfunction "GND-LED_4") (pintype "unspecified"))
      (node (ref "SW37") (pin "4") (pinfunction "GND-LED_4") (pintype "unspecified"))
    )
    (net (code "93") (name "Net-(SW38-GND-LED)") (class "Default")
      (node (ref "R9") (pin "2") (pinfunction "2_2") (pintype "unspecified"))
      (node (ref "SW38") (pin "4") (pinfunction "GND-LED_4") (pintype "unspecified"))
      (node (ref "SW39") (pin "4") (pinfunction "GND-LED_4") (pintype "unspecified"))
      (node (ref "SW40") (pin "4") (pinfunction "GND-LED_4") (pintype "unspecified"))
      (node (ref "SW41") (pin "4") (pinfunction "GND-LED_4") (pintype "unspecified"))
      (node (ref "SW42") (pin "4") (pinfunction "GND-LED_4") (pintype "unspecified"))
    )
    (net (code "94") (name "Net-(SW43-GND-LED)") (class "Default")
      (node (ref "R10") (pin "2") (pinfunction "2_2") (pintype "unspecified"))
      (node (ref "SW43") (pin "4") (pinfunction "GND-LED_4") (pintype "unspecified"))
      (node (ref "SW44") (pin "4") (pinfunction "GND-LED_4") (pintype "unspecified"))
      (node (ref "SW45") (pin "4") (pinfunction "GND-LED_4") (pintype "unspecified"))
      (node (ref "SW46") (pin "4") (pinfunction "GND-LED_4") (pintype "unspecified"))
      (node (ref "SW47") (pin "4") (pinfunction "GND-LED_4") (pintype "unspecified"))
    )
    (net (code "95") (name "Net-(SW48-GND-LED)") (class "Default")
      (node (ref "R11") (pin "2") (pinfunction "2_2") (pintype "unspecified"))
      (node (ref "SW48") (pin "4") (pinfunction "GND-LED_4") (pintype "unspecified"))
      (node (ref "SW49") (pin "4") (pinfunction "GND-LED_4") (pintype "unspecified"))
      (node (ref "SW50") (pin "4") (pinfunction "GND-LED_4") (pintype "unspecified"))
      (node (ref "SW51") (pin "4") (pinfunction "GND-LED_4") (pintype "unspecified"))
      (node (ref "SW52") (pin "4") (pinfunction "GND-LED_4") (pintype "unspecified"))
    )
    (net (code "96") (name "Net-(SW53-GND-LED)") (class "Default")
      (node (ref "R12") (pin "2") (pinfunction "2_2") (pintype "unspecified"))
      (node (ref "SW53") (pin "4") (pinfunction "GND-LED_4") (pintype "unspecified"))
      (node (ref "SW54") (pin "4") (pinfunction "GND-LED_4") (pintype "unspecified"))
      (node (ref "SW55") (pin "4") (pinfunction "GND-LED_4") (pintype "unspecified"))
      (node (ref "SW56") (pin "4") (pinfunction "GND-LED_4") (pintype "unspecified"))
      (node (ref "SW57") (pin "4") (pinfunction "GND-LED_4") (pintype "unspecified"))
    )
    (net (code "97") (name "Net-(SW58-GND-LED)") (class "Default")
      (node (ref "R13") (pin "2") (pinfunction "2_2") (pintype "unspecified"))
      (node (ref "SW58") (pin "4") (pinfunction "GND-LED_4") (pintype "unspecified"))
      (node (ref "SW59") (pin "4") (pinfunction "GND-LED_4") (pintype "unspecified"))
      (node (ref "SW60") (pin "4") (pinfunction "GND-LED_4") (pintype "unspecified"))
      (node (ref "SW61") (pin "4") (pinfunction "GND-LED_4") (pintype "unspecified"))
      (node (ref "SW62") (pin "4") (pinfunction "GND-LED_4") (pintype "unspecified"))
    )
    (net (code "98") (name "Net-(SW63-GND-LED)") (class "Default")
      (node (ref "R14") (pin "2") (pinfunction "2_2") (pintype "unspecified"))
      (node (ref "SW63") (pin "4") (pinfunction "GND-LED_4") (pintype "unspecified"))
      (node (ref "SW64") (pin "4") (pinfunction "GND-LED_4") (pintype "unspecified"))
      (node (ref "SW65") (pin "4") (pinfunction "GND-LED_4") (pintype "unspecified"))
      (node (ref "SW66") (pin "4") (pinfunction "GND-LED_4") (pintype "unspecified"))
      (node (ref "SW67") (pin "4") (pinfunction "GND-LED_4") (pintype "unspecified"))
    )
    (net (code "99") (name "Net-(U1-AREF)") (class "Default")
      (node (ref "C14") (pin "1") (pinfunction "1_1") (pintype "unspecified"))
      (node (ref "U1") (pin "42") (pinfunction "AREF_42") (pintype "unspecified"))
    )
    (net (code "100") (name "Net-(U1-D+)") (class "Default")
      (node (ref "R21") (pin "1") (pinfunction "1_1") (pintype "input"))
      (node (ref "U1") (pin "4") (pinfunction "D+_4") (pintype "unspecified"))
    )
    (net (code "101") (name "Net-(U1-D-)") (class "Default")
      (node (ref "R20") (pin "1") (pinfunction "1_1") (pintype "input"))
      (node (ref "U1") (pin "3") (pinfunction "D-_3") (pintype "unspecified"))
    )
    (net (code "102") (name "Net-(U1-PE2(HWB#))") (class "Default")
      (node (ref "R23") (pin "2") (pinfunction "2_2") (pintype "input"))
      (node (ref "U1") (pin "33") (pinfunction "PE2(HWB#)_33") (pintype "unspecified"))
    )
    (net (code "103") (name "Net-(U1-UCap)") (class "Default")
      (node (ref "C13") (pin "2") (pinfunction "2_2") (pintype "input"))
      (node (ref "U1") (pin "6") (pinfunction "UCap_6") (pintype "unspecified"))
    )
    (net (code "104") (name "Net-(U1-XTAL1)") (class "Default")
      (node (ref "C11") (pin "2") (pinfunction "2_2") (pintype "input"))
      (node (ref "U1") (pin "17") (pinfunction "XTAL1_17") (pintype "unspecified"))
      (node (ref "X1") (pin "1") (pinfunction "OSC1_1") (pintype "unspecified"))
    )
    (net (code "105") (name "Net-(U1-XTAL2)") (class "Default")
      (node (ref "C12") (pin "2") (pinfunction "2_2") (pintype "input"))
      (node (ref "U1") (pin "16") (pinfunction "XTAL2_16") (pintype "unspecified"))
      (node (ref "X1") (pin "3") (pinfunction "OSC2_3") (pintype "unspecified"))
    )
    (net (code "106") (name "Net-(USBC1-CC1)") (class "Default")
      (node (ref "R24") (pin "1") (pinfunction "1_1") (pintype "unspecified"))
      (node (ref "USBC1") (pin "A5") (pinfunction "CC1_A5") (pintype "unspecified"))
    )
    (net (code "107") (name "Net-(USBC1-CC2)") (class "Default")
      (node (ref "R22") (pin "2") (pinfunction "2_2") (pintype "unspecified"))
      (node (ref "USBC1") (pin "B5") (pinfunction "CC2_B5") (pintype "unspecified"))
    )
    (net (code "108") (name "Reset") (class "Default")
      (node (ref "HEADER") (pin "1") (pinfunction "RST_1") (pintype "unspecified"))
      (node (ref "R19") (pin "2") (pinfunction "2_2") (pintype "input"))
      (node (ref "SW68") (pin "1") (pinfunction "A_1") (pintype "unspecified"))
      (node (ref "SW68") (pin "2") (pinfunction "B_2") (pintype "unspecified"))
      (node (ref "U1") (pin "13") (pinfunction "RESET#_13") (pintype "unspecified"))
      (node (ref "U3") (pin "1") (pinfunction "._1") (pintype "unspecified"))
    )
    (net (code "109") (name "Row0") (class "Default")
      (node (ref "D1") (pin "1") (pinfunction "K_1") (pintype "unspecified"))
      (node (ref "D10") (pin "1") (pinfunction "K_1") (pintype "unspecified"))
      (node (ref "D11") (pin "1") (pinfunction "K_1") (pintype "unspecified"))
      (node (ref "D15") (pin "1") (pinfunction "K_1") (pintype "unspecified"))
      (node (ref "D16") (pin "1") (pinfunction "K_1") (pintype "unspecified"))
      (node (ref "D20") (pin "1") (pinfunction "K_1") (pintype "unspecified"))
      (node (ref "D21") (pin "1") (pinfunction "K_1") (pintype "unspecified"))
      (node (ref "D25") (pin "1") (pinfunction "K_1") (pintype "unspecified"))
      (node (ref "D26") (pin "1") (pinfunction "K_1") (pintype "unspecified"))
      (node (ref "D30") (pin "1") (pinfunction "K_1") (pintype "unspecified"))
      (node (ref "D31") (pin "1") (pinfunction "K_1") (pintype "unspecified"))
      (node (ref "D35") (pin "1") (pinfunction "K_1") (pintype "unspecified"))
      (node (ref "D36") (pin "1") (pinfunction "K_1") (pintype "unspecified"))
      (node (ref "D40") (pin "1") (pinfunction "K_1") (pintype "unspecified"))
      (node (ref "D41") (pin "1") (pinfunction "K_1") (pintype "unspecified"))
      (node (ref "D45") (pin "1") (pinfunction "K_1") (pintype "unspecified"))
      (node (ref "D46") (pin "1") (pinfunction "K_1") (pintype "unspecified"))
      (node (ref "D5") (pin "1") (pinfunction "K_1") (pintype "unspecified"))
      (node (ref "D50") (pin "1") (pinfunction "K_1") (pintype "unspecified"))
      (node (ref "D51") (pin "1") (pinfunction "K_1") (pintype "unspecified"))
      (node (ref "D55") (pin "1") (pinfunction "K_1") (pintype "unspecified"))
      (node (ref "D56") (pin "1") (pinfunction "K_1") (pintype "unspecified"))
      (node (ref "D6") (pin "1") (pinfunction "K_1") (pintype "unspecified"))
      (node (ref "D60") (pin "1") (pinfunction "K_1") (pintype "unspecified"))
      (node (ref "D61") (pin "1") (pinfunction "K_1") (pintype "unspecified"))
      (node (ref "D65") (pin "1") (pinfunction "K_1") (pintype "unspecified"))
      (node (ref "D66") (pin "1") (pinfunction "K_1") (pintype "unspecified"))
      (node (ref "D70") (pin "1") (pinfunction "K_1") (pintype "unspecified"))
      (node (ref "U1") (pin "12") (pinfunction "PB7(PCINT7/OC0A/OC1C/RTS#)_12") (pintype "unspecified"))
    )
    (net (code "110") (name "Row1") (class "Default")
      (node (ref "D12") (pin "1") (pinfunction "K_1") (pintype "unspecified"))
      (node (ref "D13") (pin "1") (pinfunction "K_1") (pintype "unspecified"))
      (node (ref "D17") (pin "1") (pinfunction "K_1") (pintype "unspecified"))
      (node (ref "D18") (pin "1") (pinfunction "K_1") (pintype "unspecified"))
      (node (ref "D2") (pin "1") (pinfunction "K_1") (pintype "unspecified"))
      (node (ref "D22") (pin "1") (pinfunction "K_1") (pintype "unspecified"))
      (node (ref "D23") (pin "1") (pinfunction "K_1") (pintype "unspecified"))
      (node (ref "D27") (pin "1") (pinfunction "K_1") (pintype "unspecified"))
      (node (ref "D28") (pin "1") (pinfunction "K_1") (pintype "unspecified"))
      (node (ref "D3") (pin "1") (pinfunction "K_1") (pintype "unspecified"))
      (node (ref "D32") (pin "1") (pinfunction "K_1") (pintype "unspecified"))
      (node (ref "D33") (pin "1") (pinfunction "K_1") (pintype "unspecified"))
      (node (ref "D37") (pin "1") (pinfunction "K_1") (pintype "unspecified"))
      (node (ref "D38") (pin "1") (pinfunction "K_1") (pintype "unspecified"))
      (node (ref "D42") (pin "1") (pinfunction "K_1") (pintype "unspecified"))
      (node (ref "D43") (pin "1") (pinfunction "K_1") (pintype "unspecified"))
      (node (ref "D47") (pin "1") (pinfunction "K_1") (pintype "unspecified"))
      (node (ref "D48") (pin "1") (pinfunction "K_1") (pintype "unspecified"))
      (node (ref "D52") (pin "1") (pinfunction "K_1") (pintype "unspecified"))
      (node (ref "D53") (pin "1") (pinfunction "K_1") (pintype "unspecified"))
      (node (ref "D57") (pin "1") (pinfunction "K_1") (pintype "unspecified"))
      (node (ref "D58") (pin "1") (pinfunction "K_1") (pintype "unspecified"))
      (node (ref "D62") (pin "1") (pinfunction "K_1") (pintype "unspecified"))
      (node (ref "D63") (pin "1") (pinfunction "K_1") (pintype "unspecified"))
      (node (ref "D67") (pin "1") (pinfunction "K_1") (pintype "unspecified"))
      (node (ref "D68") (pin "1") (pinfunction "K_1") (pintype "unspecified"))
      (node (ref "D7") (pin "1") (pinfunction "K_1") (pintype "unspecified"))
      (node (ref "D8") (pin "1") (pinfunction "K_1") (pintype "unspecified"))
      (node (ref "U1") (pin "25") (pinfunction "PD4(ICP1/ADC8)_25") (pintype "unspecified"))
    )
    (net (code "111") (name "Row2") (class "Default")
      (node (ref "D14") (pin "1") (pinfunction "K_1") (pintype "unspecified"))
      (node (ref "D19") (pin "1") (pinfunction "K_1") (pintype "unspecified"))
      (node (ref "D24") (pin "1") (pinfunction "K_1") (pintype "unspecified"))
      (node (ref "D29") (pin "1") (pinfunction "K_1") (pintype "unspecified"))
      (node (ref "D34") (pin "1") (pinfunction "K_1") (pintype "unspecified"))
      (node (ref "D39") (pin "1") (pinfunction "K_1") (pintype "unspecified"))
      (node (ref "D4") (pin "1") (pinfunction "K_1") (pintype "unspecified"))
      (node (ref "D44") (pin "1") (pinfunction "K_1") (pintype "unspecified"))
      (node (ref "D49") (pin "1") (pinfunction "K_1") (pintype "unspecified"))
      (node (ref "D54") (pin "1") (pinfunction "K_1") (pintype "unspecified"))
      (node (ref "D59") (pin "1") (pinfunction "K_1") (pintype "unspecified"))
      (node (ref "D64") (pin "1") (pinfunction "K_1") (pintype "unspecified"))
      (node (ref "D69") (pin "1") (pinfunction "K_1") (pintype "unspecified"))
      (node (ref "D9") (pin "1") (pinfunction "K_1") (pintype "unspecified"))
      (node (ref "U1") (pin "26") (pinfunction "PD6(T1/OC4D#/ADC9)_26") (pintype "unspecified"))
    )
    (net (code "112") (name "SCLK") (class "Default")
      (node (ref "HEADER") (pin "2") (pinfunction "SCLK_2") (pintype "unspecified"))
      (node (ref "OLED1") (pin "2") (pinfunction "SCL_2") (pintype "unspecified"))
      (node (ref "U1") (pin "9") (pinfunction "PB1(PCINT1/SCLK)_9") (pintype "unspecified"))
      (node (ref "U2") (pin "2") (pinfunction "._2") (pintype "unspecified"))
      (node (ref "U3") (pin "2") (pinfunction "._2") (pintype "unspecified"))
    )
    (net (code "113") (name "SDA") (class "Default")
      (node (ref "OLED1") (pin "1") (pinfunction "SDA_1") (pintype "unspecified"))
      (node (ref "U1") (pin "19") (pinfunction "PD1(SDA/INT1)_19") (pintype "unspecified"))
      (node (ref "U2") (pin "1") (pinfunction "._1") (pintype "unspecified"))
    )
    (net (code "114") (name "VCC") (class "Default")
      (node (ref "C15") (pin "2") (pinfunction "2_2") (pintype "input"))
      (node (ref "C16") (pin "2") (pinfunction "2_2") (pintype "unspecified"))
      (node (ref "C17") (pin "2") (pinfunction "2_2") (pintype "unspecified"))
      (node (ref "C18") (pin "2") (pinfunction "2_2") (pintype "unspecified"))
      (node (ref "C19") (pin "2") (pinfunction "2_2") (pintype "unspecified"))
      (node (ref "C20") (pin "2") (pinfunction "2_2") (pintype "unspecified"))
      (node (ref "ESD1") (pin "5") (pinfunction "VBUS_5") (pintype "unspecified"))
      (node (ref "OLED1") (pin "3") (pinfunction "Vcc_3") (pintype "unspecified"))
      (node (ref "PWR1") (pin "1") (pinfunction "A_1") (pintype "unspecified"))
      (node (ref "R19") (pin "1") (pinfunction "1_1") (pintype "input"))
      (node (ref "SW69") (pin "4") (pinfunction "B1_4") (pintype "input"))
      (node (ref "U1") (pin "14") (pinfunction "VCC_14") (pintype "unspecified"))
      (node (ref "U1") (pin "2") (pinfunction "UVcc_2") (pintype "unspecified"))
      (node (ref "U1") (pin "24") (pinfunction "AVCC_24") (pintype "unspecified"))
      (node (ref "U1") (pin "34") (pinfunction "VCC_34") (pintype "unspecified"))
      (node (ref "U1") (pin "44") (pinfunction "AVCC_44") (pintype "unspecified"))
      (node (ref "U1") (pin "7") (pinfunction "VBus_7") (pintype "unspecified"))
      (node (ref "U2") (pin "3") (pinfunction "._3") (pintype "unspecified"))
      (node (ref "USBC1") (pin "A4") (pinfunction "VBUS_A4") (pintype "unspecified"))
      (node (ref "USBC1") (pin "A9") (pinfunction "VBUS_A9") (pintype "unspecified"))
    )
    (net (code "115") (name "en1_A") (class "Default")
      (node (ref "C2") (pin "2") (pinfunction "2_2") (pintype "unspecified"))
      (node (ref "ENC1") (pin "A") (pinfunction "A_A") (pintype "unspecified"))
      (node (ref "U1") (pin "29") (pinfunction "PB5(PCINT5/OC1A/OC4B#/ADC12)_29") (pintype "unspecified"))
    )
    (net (code "116") (name "en1_B") (class "Default")
      (node (ref "C1") (pin "1") (pinfunction "1_1") (pintype "unspecified"))
      (node (ref "ENC1") (pin "B") (pinfunction "B_B") (pintype "unspecified"))
      (node (ref "U1") (pin "30") (pinfunction "PB6(PCINT6/OC1B/OC4B/ADC13)_30") (pintype "unspecified"))
    )
    (net (code "117") (name "en2_A") (class "Default")
      (node (ref "C4") (pin "2") (pinfunction "2_2") (pintype "unspecified"))
      (node (ref "ENC2") (pin "A") (pinfunction "A_A") (pintype "unspecified"))
      (node (ref "U1") (pin "31") (pinfunction "PC6(OC3A/OC4A#)_31") (pintype "unspecified"))
    )
    (net (code "118") (name "en2_B") (class "Default")
      (node (ref "C3") (pin "1") (pinfunction "1_1") (pintype "unspecified"))
      (node (ref "ENC2") (pin "B") (pinfunction "B_B") (pintype "unspecified"))
      (node (ref "U1") (pin "32") (pinfunction "PC7(ICP3/CLK0/OC4A)_32") (pintype "unspecified"))
    )
    (net (code "119") (name "en3_A") (class "Default")
      (node (ref "C6") (pin "2") (pinfunction "2_2") (pintype "unspecified"))
      (node (ref "ENC3") (pin "A") (pinfunction "A_A") (pintype "unspecified"))
      (node (ref "U1") (pin "36") (pinfunction "PF7(ADC7/TDI)_36") (pintype "unspecified"))
    )
    (net (code "120") (name "en3_B") (class "Default")
      (node (ref "C5") (pin "1") (pinfunction "1_1") (pintype "unspecified"))
      (node (ref "ENC3") (pin "B") (pinfunction "B_B") (pintype "unspecified"))
      (node (ref "U1") (pin "37") (pinfunction "PF6(ADC6/TDO)_37") (pintype "unspecified"))
    )
    (net (code "121") (name "en4_A") (class "Default")
      (node (ref "C8") (pin "2") (pinfunction "2_2") (pintype "unspecified"))
      (node (ref "ENC4") (pin "A") (pinfunction "A_A") (pintype "unspecified"))
      (node (ref "U1") (pin "38") (pinfunction "PF5(ADC5/TMS)_38") (pintype "unspecified"))
    )
    (net (code "122") (name "en4_B") (class "Default")
      (node (ref "C7") (pin "1") (pinfunction "1_1") (pintype "unspecified"))
      (node (ref "ENC4") (pin "B") (pinfunction "B_B") (pintype "unspecified"))
      (node (ref "U1") (pin "39") (pinfunction "PF4(ADC4/TCK)_39") (pintype "unspecified"))
    )
    (net (code "123") (name "en5_A") (class "Default")
      (node (ref "C10") (pin "2") (pinfunction "2_2") (pintype "unspecified"))
      (node (ref "ENC5") (pin "A") (pinfunction "A_A") (pintype "unspecified"))
      (node (ref "U1") (pin "40") (pinfunction "PF1(ADC1)_40") (pintype "unspecified"))
    )
    (net (code "124") (name "en5_B") (class "Default")
      (node (ref "C9") (pin "1") (pinfunction "1_1") (pintype "unspecified"))
      (node (ref "ENC5") (pin "B") (pinfunction "B_B") (pintype "unspecified"))
      (node (ref "U1") (pin "41") (pinfunction "PF0(ADC0)_41") (pintype "unspecified"))
    )
    (net (code "125") (name "gpio1") (class "Default")
      (node (ref "SW69") (pin "3") (pinfunction "B2_3") (pintype "input"))
      (node (ref "U1") (pin "27") (pinfunction "PD7(T0/OC4D/ADC10)_27") (pintype "unspecified"))
    )
    (net (code "126") (name "unconnected-(ENC1-Pad6)") (class "Default")
      (node (ref "ENC1") (pin "6") (pinfunction "6_6") (pintype "unspecified+no_connect"))
    )
    (net (code "127") (name "unconnected-(ENC1-Pad7)") (class "Default")
      (node (ref "ENC1") (pin "7") (pinfunction "7_7") (pintype "unspecified+no_connect"))
    )
    (net (code "128") (name "unconnected-(ENC2-Pad6)") (class "Default")
      (node (ref "ENC2") (pin "6") (pinfunction "6_6") (pintype "unspecified+no_connect"))
    )
    (net (code "129") (name "unconnected-(ENC2-Pad7)") (class "Default")
      (node (ref "ENC2") (pin "7") (pinfunction "7_7") (pintype "unspecified+no_connect"))
    )
    (net (code "130") (name "unconnected-(ENC3-Pad6)") (class "Default")
      (node (ref "ENC3") (pin "6") (pinfunction "6_6") (pintype "unspecified+no_connect"))
    )
    (net (code "131") (name "unconnected-(ENC3-Pad7)") (class "Default")
      (node (ref "ENC3") (pin "7") (pinfunction "7_7") (pintype "unspecified+no_connect"))
    )
    (net (code "132") (name "unconnected-(ENC4-Pad6)") (class "Default")
      (node (ref "ENC4") (pin "6") (pinfunction "6_6") (pintype "unspecified+no_connect"))
    )
    (net (code "133") (name "unconnected-(ENC4-Pad7)") (class "Default")
      (node (ref "ENC4") (pin "7") (pinfunction "7_7") (pintype "unspecified+no_connect"))
    )
    (net (code "134") (name "unconnected-(ENC5-Pad6)") (class "Default")
      (node (ref "ENC5") (pin "6") (pinfunction "6_6") (pintype "unspecified+no_connect"))
    )
    (net (code "135") (name "unconnected-(ENC5-Pad7)") (class "Default")
      (node (ref "ENC5") (pin "7") (pinfunction "7_7") (pintype "unspecified+no_connect"))
    )
    (net (code "136") (name "unconnected-(U1-PE6(INT.6{slash}AIN0)-Pad1)") (class "Default")
      (node (ref "U1") (pin "1") (pinfunction "PE6(INT.6/AIN0)_1") (pintype "unspecified+no_connect"))
    )
    (net (code "137") (name "unconnected-(USBC1-Pad0)") (class "Default")
      (node (ref "USBC1") (pin "0") (pinfunction "0_0") (pintype "unspecified+no_connect"))
    )
    (net (code "138") (name "unconnected-(USBC1-Pad0)_1") (class "Default")
      (node (ref "USBC1") (pin "0") (pinfunction "0_0") (pintype "unspecified+no_connect"))
    )
    (net (code "139") (name "unconnected-(USBC1-Pad0)_2") (class "Default")
      (node (ref "USBC1") (pin "0") (pinfunction "0_0") (pintype "unspecified+no_connect"))
    )
    (net (code "140") (name "unconnected-(USBC1-Pad0)_3") (class "Default")
      (node (ref "USBC1") (pin "0") (pinfunction "0_0") (pintype "unspecified+no_connect"))
    )
    (net (code "141") (name "unconnected-(USBC1-SBU1-PadA8)") (class "Default")
      (node (ref "USBC1") (pin "A8") (pinfunction "SBU1_A8") (pintype "unspecified+no_connect"))
    )
    (net (code "142") (name "unconnected-(USBC1-SBU2-PadB8)") (class "Default")
      (node (ref "USBC1") (pin "B8") (pinfunction "SBU2_B8") (pintype "unspecified+no_connect"))
    )
  )
)
